# pressure_mat_try1.net
KiCad netlist of a schematic drawn in EAGLE
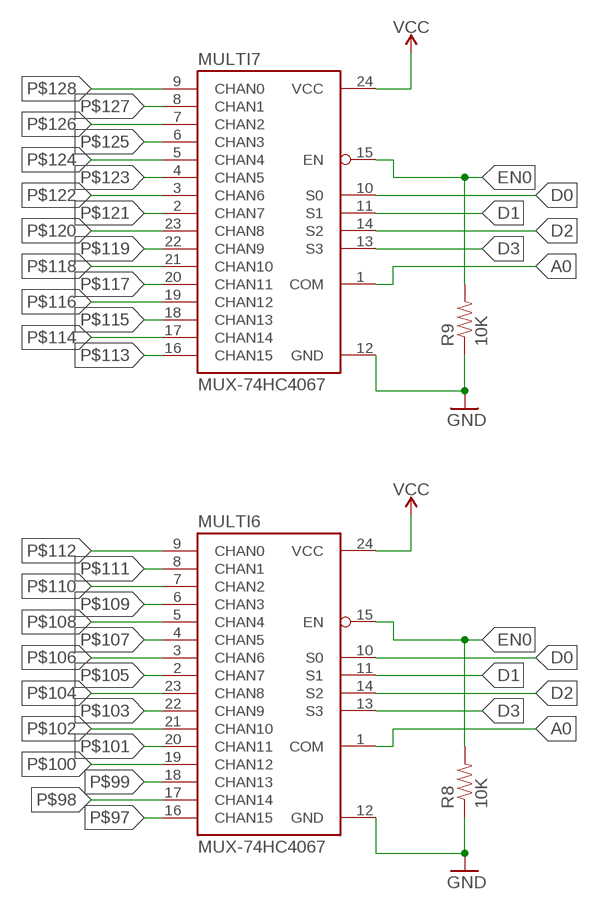
[diagram p0: schematic, sheet 1, part 1 of 3]
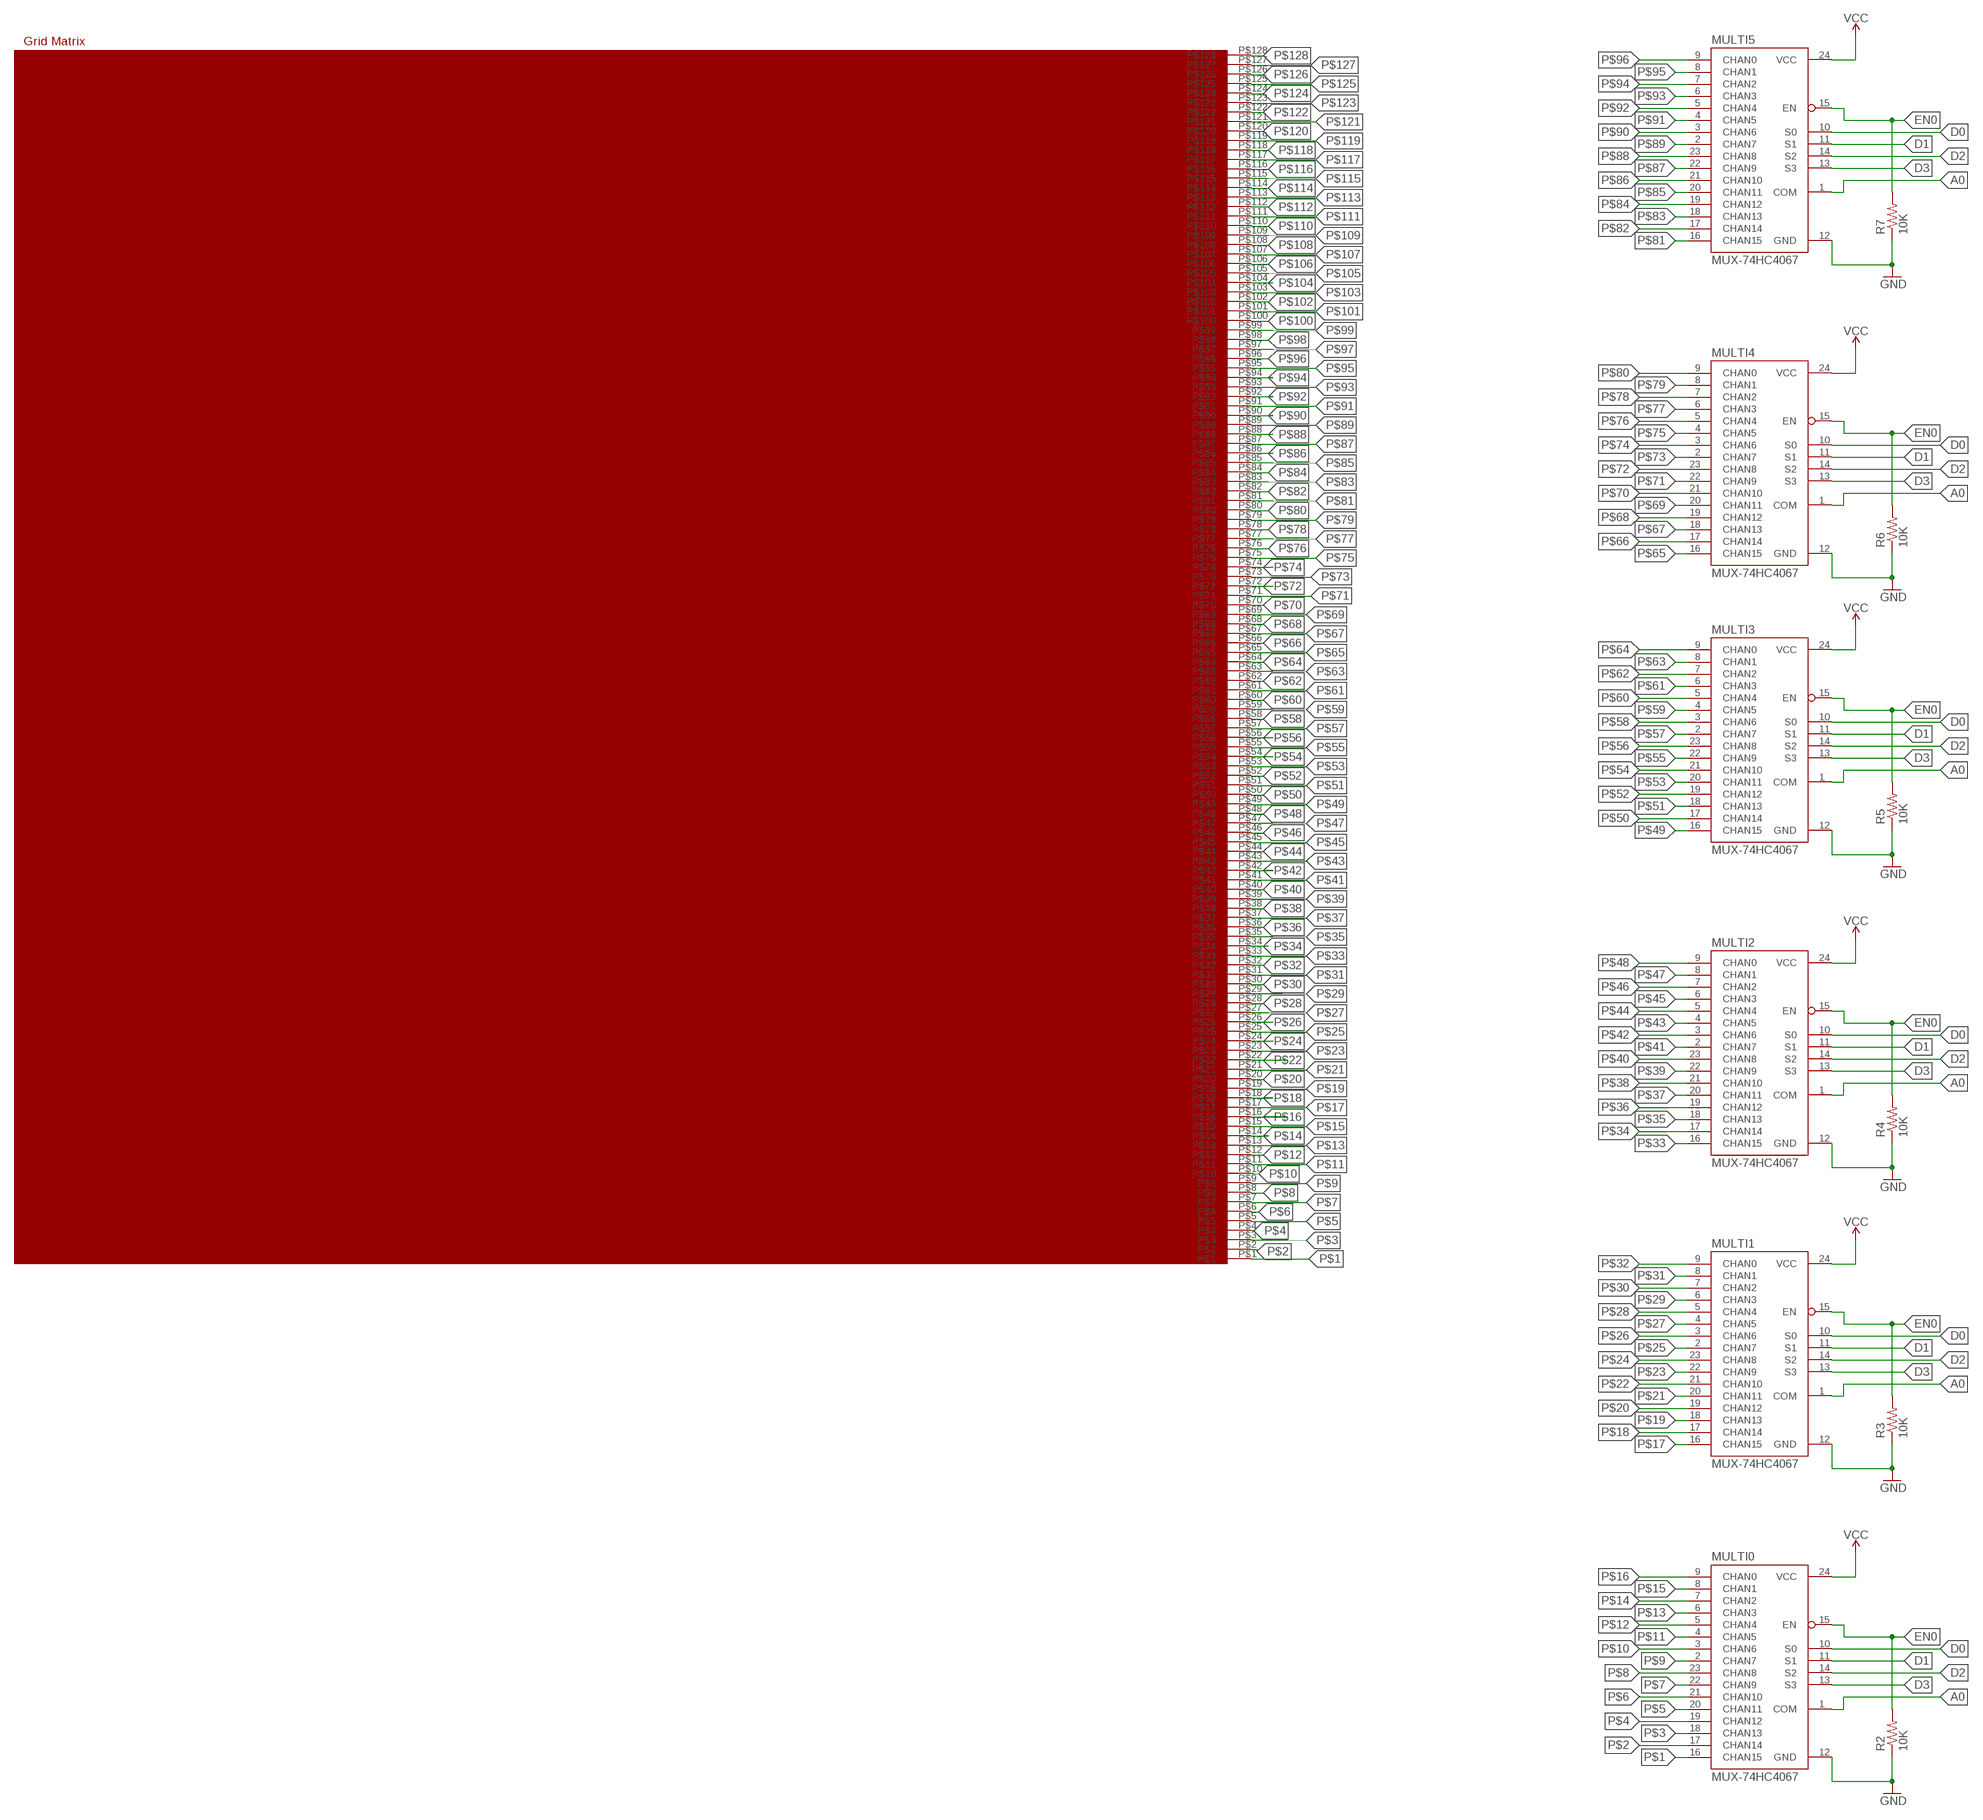
[diagram p1: schematic, sheet 1, part 2 of 3]
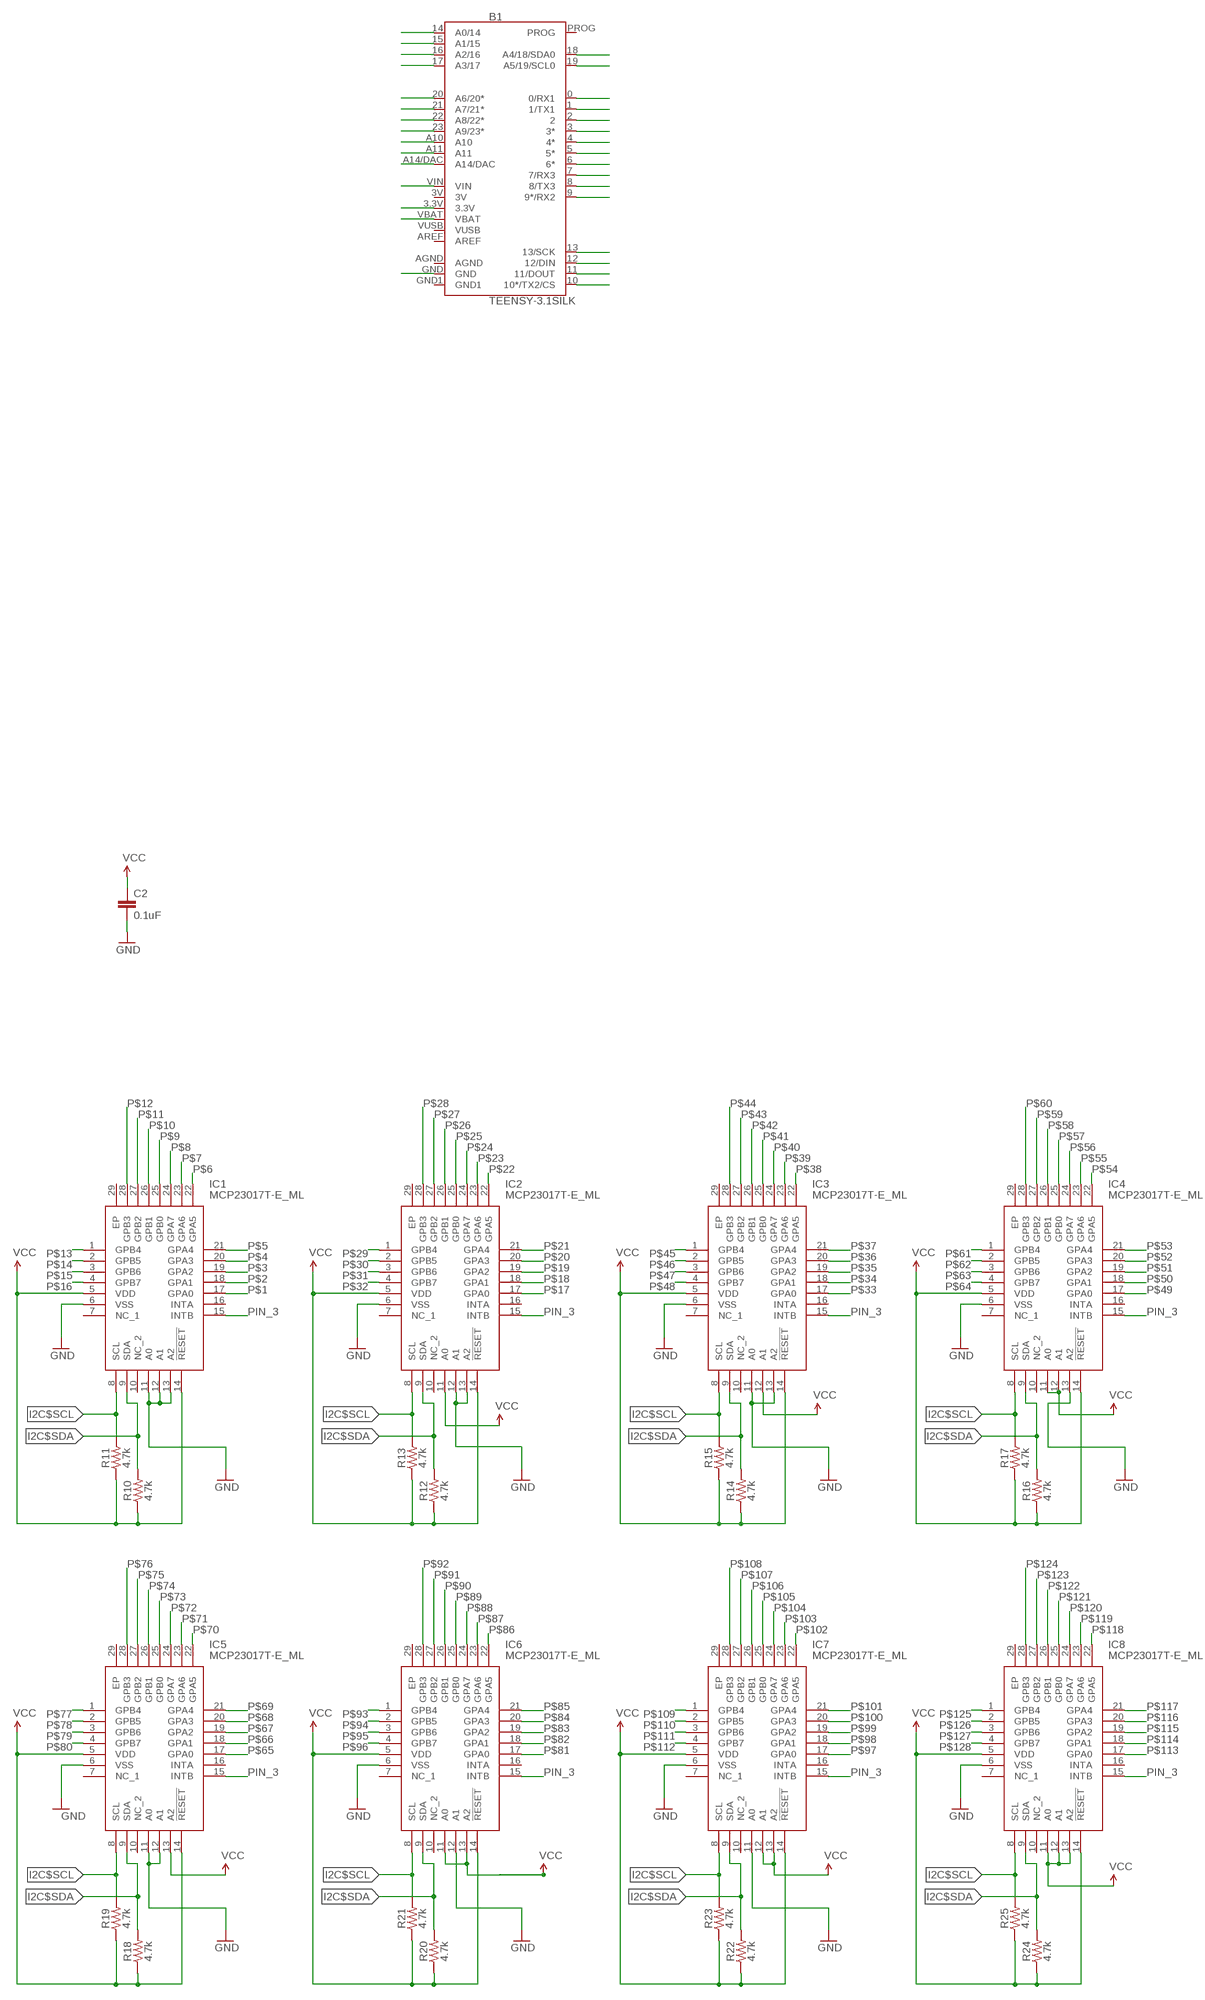
[diagram p2: schematic, sheet 1, part 3 of 3]
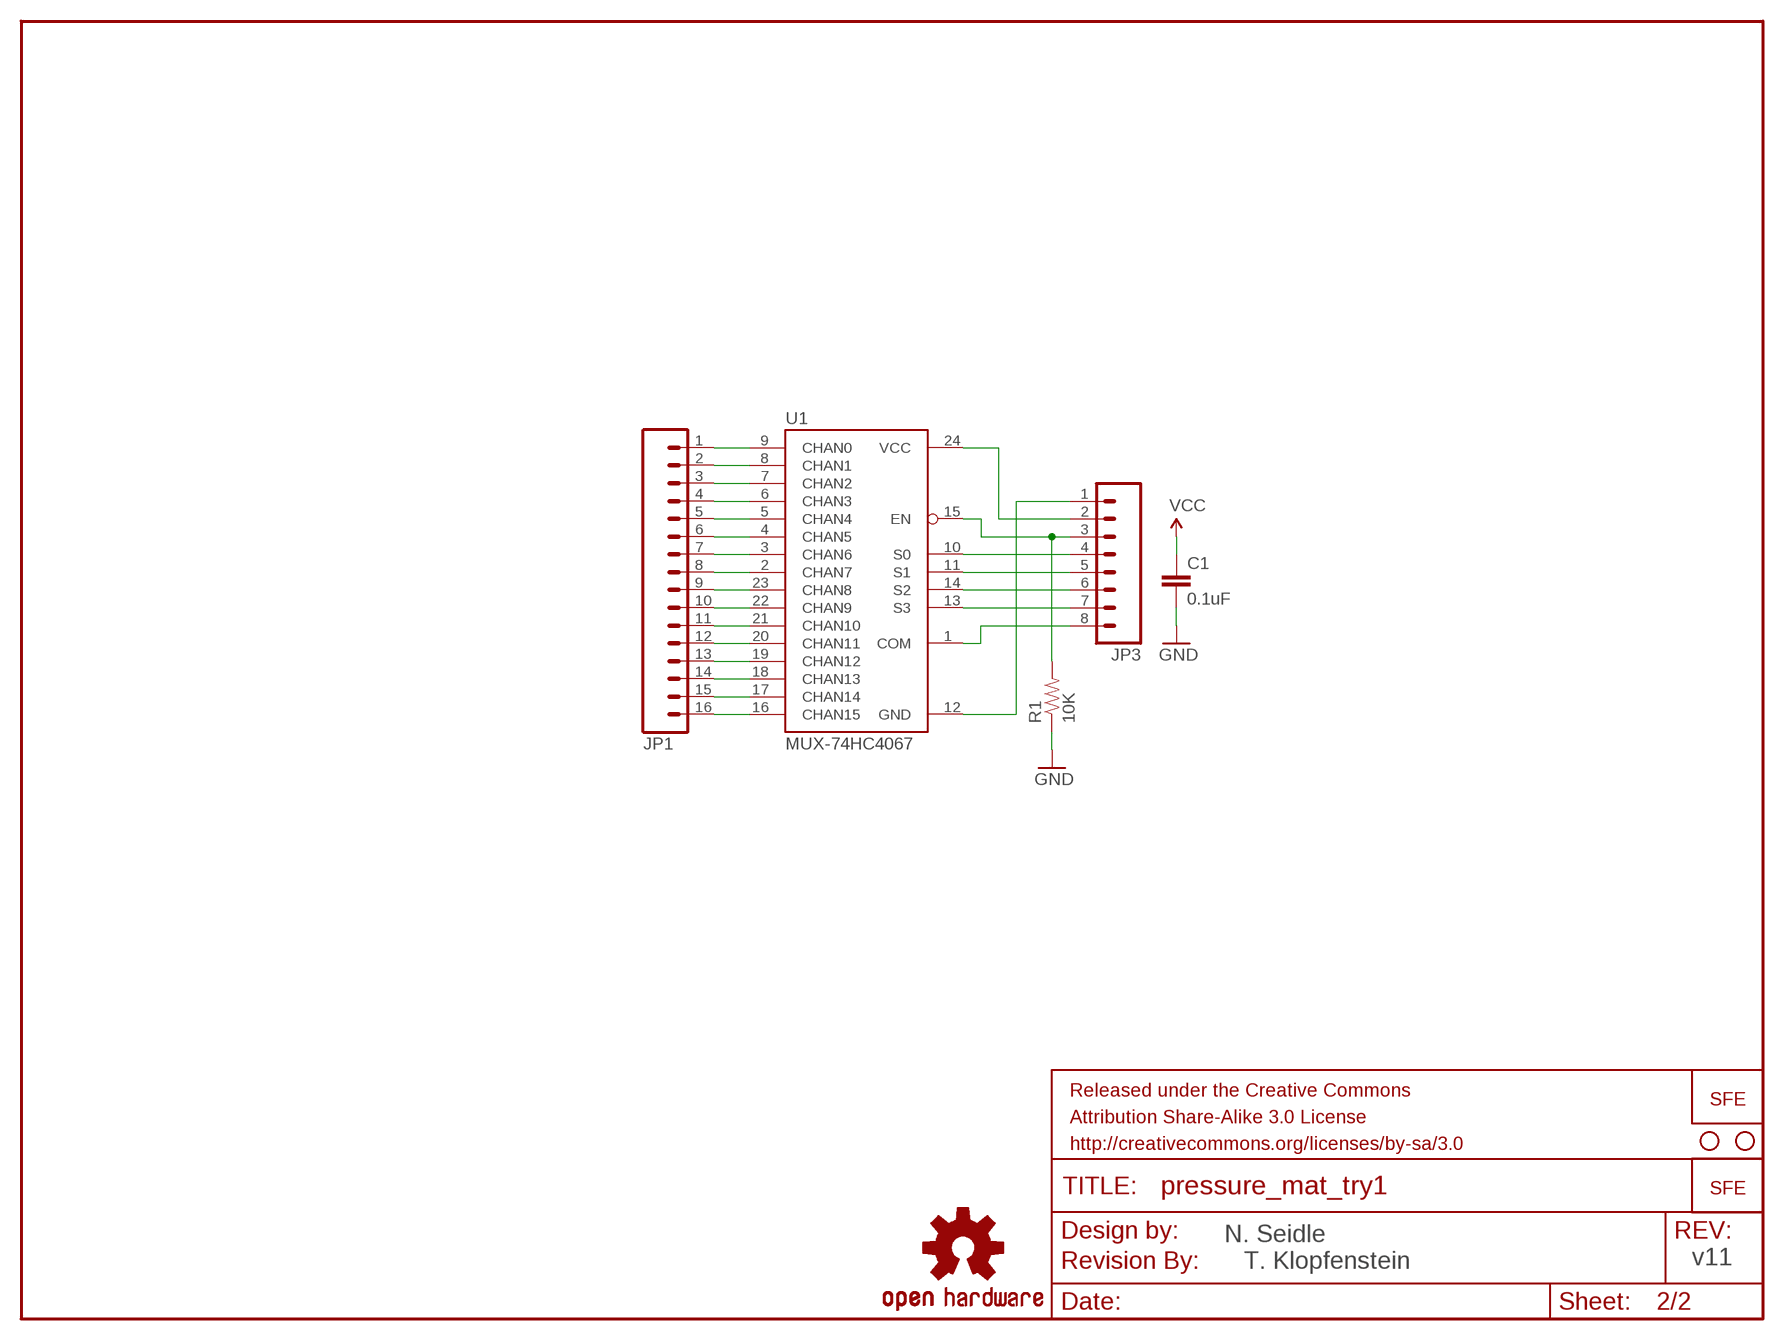
[diagram p3: schematic, sheet 2]

(export (version "E")
  (design (tool "Eeschema 10.0.6"))
  (components
    (comp (ref "B1")
      (value "TEENSY-3.1SILK")
      (footprint "eagle-import:TEENSY-3.1")
      (libsource (lib "eagle-import") (part "TEENSY-3.1SILK"))
    )
    (comp (ref "C2")
      (value "0.1uF")
      (footprint "eagle-import:0603")
      (libsource (lib "eagle-import") (part "CAP0603"))
    )
    (comp (ref "IC1")
      (value "MCP23017T-E_ML")
      (footprint "eagle-import:QFN65P600X600X100-29N")
      (fields
        (field (name "MANUFACTURER_PART_NUMBER") "MCP23017T-E/ML")
        (field (name "MOUSER_PART_NUMBER") "579-MCP23017T-E/ML")
      )
      (libsource (lib "eagle-import") (part "MCP23017T-E_ML"))
    )
    (comp (ref "IC2")
      (value "MCP23017T-E_ML")
      (footprint "eagle-import:QFN65P600X600X100-29N")
      (fields
        (field (name "MANUFACTURER_PART_NUMBER") "MCP23017T-E/ML")
        (field (name "MOUSER_PART_NUMBER") "579-MCP23017T-E/ML")
      )
      (libsource (lib "eagle-import") (part "MCP23017T-E_ML"))
    )
    (comp (ref "IC3")
      (value "MCP23017T-E_ML")
      (footprint "eagle-import:QFN65P600X600X100-29N")
      (fields
        (field (name "MANUFACTURER_PART_NUMBER") "MCP23017T-E/ML")
        (field (name "MOUSER_PART_NUMBER") "579-MCP23017T-E/ML")
      )
      (libsource (lib "eagle-import") (part "MCP23017T-E_ML"))
    )
    (comp (ref "IC4")
      (value "MCP23017T-E_ML")
      (footprint "eagle-import:QFN65P600X600X100-29N")
      (fields
        (field (name "MANUFACTURER_PART_NUMBER") "MCP23017T-E/ML")
        (field (name "MOUSER_PART_NUMBER") "579-MCP23017T-E/ML")
      )
      (libsource (lib "eagle-import") (part "MCP23017T-E_ML"))
    )
    (comp (ref "IC5")
      (value "MCP23017T-E_ML")
      (footprint "eagle-import:QFN65P600X600X100-29N")
      (fields
        (field (name "MANUFACTURER_PART_NUMBER") "MCP23017T-E/ML")
        (field (name "MOUSER_PART_NUMBER") "579-MCP23017T-E/ML")
      )
      (libsource (lib "eagle-import") (part "MCP23017T-E_ML"))
    )
    (comp (ref "IC6")
      (value "MCP23017T-E_ML")
      (footprint "eagle-import:QFN65P600X600X100-29N")
      (fields
        (field (name "MANUFACTURER_PART_NUMBER") "MCP23017T-E/ML")
        (field (name "MOUSER_PART_NUMBER") "579-MCP23017T-E/ML")
      )
      (libsource (lib "eagle-import") (part "MCP23017T-E_ML"))
    )
    (comp (ref "IC7")
      (value "MCP23017T-E_ML")
      (footprint "eagle-import:QFN65P600X600X100-29N")
      (fields
        (field (name "MANUFACTURER_PART_NUMBER") "MCP23017T-E/ML")
        (field (name "MOUSER_PART_NUMBER") "579-MCP23017T-E/ML")
      )
      (libsource (lib "eagle-import") (part "MCP23017T-E_ML"))
    )
    (comp (ref "IC8")
      (value "MCP23017T-E_ML")
      (footprint "eagle-import:QFN65P600X600X100-29N")
      (fields
        (field (name "MANUFACTURER_PART_NUMBER") "MCP23017T-E/ML")
        (field (name "MOUSER_PART_NUMBER") "579-MCP23017T-E/ML")
      )
      (libsource (lib "eagle-import") (part "MCP23017T-E_ML"))
    )
    (comp (ref "MULTI0")
      (value "MUX-74HC4067")
      (footprint "eagle-import:SSOP24")
      (libsource (lib "eagle-import") (part "MUX-74HC4067SMD"))
    )
    (comp (ref "MULTI1")
      (value "MUX-74HC4067")
      (footprint "eagle-import:SSOP24")
      (libsource (lib "eagle-import") (part "MUX-74HC4067SMD"))
    )
    (comp (ref "MULTI2")
      (value "MUX-74HC4067")
      (footprint "eagle-import:SSOP24")
      (libsource (lib "eagle-import") (part "MUX-74HC4067SMD"))
    )
    (comp (ref "MULTI3")
      (value "MUX-74HC4067")
      (footprint "eagle-import:SSOP24")
      (libsource (lib "eagle-import") (part "MUX-74HC4067SMD"))
    )
    (comp (ref "MULTI4")
      (value "MUX-74HC4067")
      (footprint "eagle-import:SSOP24")
      (libsource (lib "eagle-import") (part "MUX-74HC4067SMD"))
    )
    (comp (ref "MULTI5")
      (value "MUX-74HC4067")
      (footprint "eagle-import:SSOP24")
      (libsource (lib "eagle-import") (part "MUX-74HC4067SMD"))
    )
    (comp (ref "MULTI6")
      (value "MUX-74HC4067")
      (footprint "eagle-import:SSOP24")
      (libsource (lib "eagle-import") (part "MUX-74HC4067SMD"))
    )
    (comp (ref "MULTI7")
      (value "MUX-74HC4067")
      (footprint "eagle-import:SSOP24")
      (libsource (lib "eagle-import") (part "MUX-74HC4067SMD"))
    )
    (comp (ref "R2")
      (value "10K")
      (footprint "eagle-import:0603")
      (libsource (lib "eagle-import") (part "RESISTOR0603"))
    )
    (comp (ref "R3")
      (value "10K")
      (footprint "eagle-import:0603")
      (libsource (lib "eagle-import") (part "RESISTOR0603"))
    )
    (comp (ref "R4")
      (value "10K")
      (footprint "eagle-import:0603")
      (libsource (lib "eagle-import") (part "RESISTOR0603"))
    )
    (comp (ref "R5")
      (value "10K")
      (footprint "eagle-import:0603")
      (libsource (lib "eagle-import") (part "RESISTOR0603"))
    )
    (comp (ref "R6")
      (value "10K")
      (footprint "eagle-import:0603")
      (libsource (lib "eagle-import") (part "RESISTOR0603"))
    )
    (comp (ref "R7")
      (value "10K")
      (footprint "eagle-import:0603")
      (libsource (lib "eagle-import") (part "RESISTOR0603"))
    )
    (comp (ref "R8")
      (value "10K")
      (footprint "eagle-import:0603")
      (libsource (lib "eagle-import") (part "RESISTOR0603"))
    )
    (comp (ref "R9")
      (value "10K")
      (footprint "eagle-import:0603")
      (libsource (lib "eagle-import") (part "RESISTOR0603"))
    )
    (comp (ref "R10")
      (value "4.7k")
      (footprint "eagle-import:0603")
      (libsource (lib "eagle-import") (part "4.7KOHM-0603-1/10W-1%"))
    )
    (comp (ref "R11")
      (value "4.7k")
      (footprint "eagle-import:0603")
      (libsource (lib "eagle-import") (part "4.7KOHM-0603-1/10W-1%"))
    )
    (comp (ref "R12")
      (value "4.7k")
      (footprint "eagle-import:0603")
      (libsource (lib "eagle-import") (part "4.7KOHM-0603-1/10W-1%"))
    )
    (comp (ref "R13")
      (value "4.7k")
      (footprint "eagle-import:0603")
      (libsource (lib "eagle-import") (part "4.7KOHM-0603-1/10W-1%"))
    )
    (comp (ref "R14")
      (value "4.7k")
      (footprint "eagle-import:0603")
      (libsource (lib "eagle-import") (part "4.7KOHM-0603-1/10W-1%"))
    )
    (comp (ref "R15")
      (value "4.7k")
      (footprint "eagle-import:0603")
      (libsource (lib "eagle-import") (part "4.7KOHM-0603-1/10W-1%"))
    )
    (comp (ref "R16")
      (value "4.7k")
      (footprint "eagle-import:0603")
      (libsource (lib "eagle-import") (part "4.7KOHM-0603-1/10W-1%"))
    )
    (comp (ref "R17")
      (value "4.7k")
      (footprint "eagle-import:0603")
      (libsource (lib "eagle-import") (part "4.7KOHM-0603-1/10W-1%"))
    )
    (comp (ref "R18")
      (value "4.7k")
      (footprint "eagle-import:0603")
      (libsource (lib "eagle-import") (part "4.7KOHM-0603-1/10W-1%"))
    )
    (comp (ref "R19")
      (value "4.7k")
      (footprint "eagle-import:0603")
      (libsource (lib "eagle-import") (part "4.7KOHM-0603-1/10W-1%"))
    )
    (comp (ref "R20")
      (value "4.7k")
      (footprint "eagle-import:0603")
      (libsource (lib "eagle-import") (part "4.7KOHM-0603-1/10W-1%"))
    )
    (comp (ref "R21")
      (value "4.7k")
      (footprint "eagle-import:0603")
      (libsource (lib "eagle-import") (part "4.7KOHM-0603-1/10W-1%"))
    )
    (comp (ref "R22")
      (value "4.7k")
      (footprint "eagle-import:0603")
      (libsource (lib "eagle-import") (part "4.7KOHM-0603-1/10W-1%"))
    )
    (comp (ref "R23")
      (value "4.7k")
      (footprint "eagle-import:0603")
      (libsource (lib "eagle-import") (part "4.7KOHM-0603-1/10W-1%"))
    )
    (comp (ref "R24")
      (value "4.7k")
      (footprint "eagle-import:0603")
      (libsource (lib "eagle-import") (part "4.7KOHM-0603-1/10W-1%"))
    )
    (comp (ref "R25")
      (value "4.7k")
      (footprint "eagle-import:0603")
      (libsource (lib "eagle-import") (part "4.7KOHM-0603-1/10W-1%"))
    )
    (comp (ref "U$3")
      (value "SENSOR_GRID_V1.0")
      (footprint "eagle-import:SENSOR_GRID_V1.0")
      (libsource (lib "eagle-import") (part "SENSOR_GRID_V1.0"))
    )
    (comp (ref "C1")
      (value "0.1uF")
      (footprint "eagle-import:0603")
      (libsource (lib "eagle-import") (part "CAP0603"))
    )
    (comp (ref "FRAME1")
      (value "FRAME-LETTER")
      (footprint "eagle-import:CREATIVE_COMMONS")
      (libsource (lib "eagle-import") (part "FRAME-LETTER"))
    )
    (comp (ref "JP1")
      (value "M16PTH")
      (footprint "eagle-import:1X16")
      (libsource (lib "eagle-import") (part "M16PTH"))
    )
    (comp (ref "JP3")
      (value "M081X08")
      (footprint "eagle-import:1X08")
      (libsource (lib "eagle-import") (part "M081X08"))
    )
    (comp (ref "LOGO1")
      (value "OSHW-LOGOL")
      (footprint "eagle-import:OSHW-LOGO-L")
      (libsource (lib "eagle-import") (part "OSHW-LOGOL"))
    )
    (comp (ref "LOGO2")
      (value "LOGO-SFESK")
      (footprint "eagle-import:SFE-LOGO-FLAME")
      (libsource (lib "eagle-import") (part "SparkFun-Aesthetics_LOGO-SFESK"))
    )
    (comp (ref "R1")
      (value "10K")
      (footprint "eagle-import:0603")
      (libsource (lib "eagle-import") (part "RESISTOR0603"))
    )
    (comp (ref "STANDOFF1")
      (value "STAND-OFF")
      (footprint "eagle-import:STAND-OFF")
      (libsource (lib "eagle-import") (part "STAND-OFF"))
    )
    (comp (ref "STANDOFF2")
      (value "STAND-OFF")
      (footprint "eagle-import:STAND-OFF")
      (libsource (lib "eagle-import") (part "STAND-OFF"))
    )
    (comp (ref "U$1")
      (value "LOGO-SFENEW")
      (footprint "eagle-import:SFE-NEW-WEBLOGO")
      (libsource (lib "eagle-import") (part "LOGO-SFENEW"))
    )
    (comp (ref "U$2")
      (value "REVISION")
      (footprint "eagle-import:REVISION")
      (libsource (lib "eagle-import") (part "REVISION"))
    )
    (comp (ref "U1")
      (value "MUX-74HC4067")
      (footprint "eagle-import:SSOP24")
      (libsource (lib "eagle-import") (part "MUX-74HC4067SMD"))
    )
  )
  (nets
    (net (code "1") (name "3V") (class "Default")
      (node (ref "B1") (pin "3V") (pinfunction "3V_3V") (pintype "power_in"))
    )
    (net (code "2") (name "A0") (class "Default")
      (node (ref "MULTI0") (pin "1") (pinfunction "COM_1") (pintype "bidirectional"))
      (node (ref "MULTI1") (pin "1") (pinfunction "COM_1") (pintype "bidirectional"))
      (node (ref "MULTI2") (pin "1") (pinfunction "COM_1") (pintype "bidirectional"))
      (node (ref "MULTI3") (pin "1") (pinfunction "COM_1") (pintype "bidirectional"))
      (node (ref "MULTI4") (pin "1") (pinfunction "COM_1") (pintype "bidirectional"))
      (node (ref "MULTI5") (pin "1") (pinfunction "COM_1") (pintype "bidirectional"))
      (node (ref "MULTI6") (pin "1") (pinfunction "COM_1") (pintype "bidirectional"))
      (node (ref "MULTI7") (pin "1") (pinfunction "COM_1") (pintype "bidirectional"))
    )
    (net (code "3") (name "AGND") (class "Default")
      (node (ref "B1") (pin "AGND") (pinfunction "AGND_AGND") (pintype "power_in"))
    )
    (net (code "4") (name "D0") (class "Default")
      (node (ref "MULTI0") (pin "10") (pinfunction "S0_10") (pintype "input"))
      (node (ref "MULTI1") (pin "10") (pinfunction "S0_10") (pintype "input"))
      (node (ref "MULTI2") (pin "10") (pinfunction "S0_10") (pintype "input"))
      (node (ref "MULTI3") (pin "10") (pinfunction "S0_10") (pintype "input"))
      (node (ref "MULTI4") (pin "10") (pinfunction "S0_10") (pintype "input"))
      (node (ref "MULTI5") (pin "10") (pinfunction "S0_10") (pintype "input"))
      (node (ref "MULTI6") (pin "10") (pinfunction "S0_10") (pintype "input"))
      (node (ref "MULTI7") (pin "10") (pinfunction "S0_10") (pintype "input"))
    )
    (net (code "5") (name "D1") (class "Default")
      (node (ref "MULTI0") (pin "11") (pinfunction "S1_11") (pintype "input"))
      (node (ref "MULTI1") (pin "11") (pinfunction "S1_11") (pintype "input"))
      (node (ref "MULTI2") (pin "11") (pinfunction "S1_11") (pintype "input"))
      (node (ref "MULTI3") (pin "11") (pinfunction "S1_11") (pintype "input"))
      (node (ref "MULTI4") (pin "11") (pinfunction "S1_11") (pintype "input"))
      (node (ref "MULTI5") (pin "11") (pinfunction "S1_11") (pintype "input"))
      (node (ref "MULTI6") (pin "11") (pinfunction "S1_11") (pintype "input"))
      (node (ref "MULTI7") (pin "11") (pinfunction "S1_11") (pintype "input"))
    )
    (net (code "6") (name "D2") (class "Default")
      (node (ref "MULTI0") (pin "14") (pinfunction "S2_14") (pintype "input"))
      (node (ref "MULTI1") (pin "14") (pinfunction "S2_14") (pintype "input"))
      (node (ref "MULTI2") (pin "14") (pinfunction "S2_14") (pintype "input"))
      (node (ref "MULTI3") (pin "14") (pinfunction "S2_14") (pintype "input"))
      (node (ref "MULTI4") (pin "14") (pinfunction "S2_14") (pintype "input"))
      (node (ref "MULTI5") (pin "14") (pinfunction "S2_14") (pintype "input"))
      (node (ref "MULTI6") (pin "14") (pinfunction "S2_14") (pintype "input"))
      (node (ref "MULTI7") (pin "14") (pinfunction "S2_14") (pintype "input"))
    )
    (net (code "7") (name "D3") (class "Default")
      (node (ref "MULTI0") (pin "13") (pinfunction "S3_13") (pintype "input"))
      (node (ref "MULTI1") (pin "13") (pinfunction "S3_13") (pintype "input"))
      (node (ref "MULTI2") (pin "13") (pinfunction "S3_13") (pintype "input"))
      (node (ref "MULTI3") (pin "13") (pinfunction "S3_13") (pintype "input"))
      (node (ref "MULTI4") (pin "13") (pinfunction "S3_13") (pintype "input"))
      (node (ref "MULTI5") (pin "13") (pinfunction "S3_13") (pintype "input"))
      (node (ref "MULTI6") (pin "13") (pinfunction "S3_13") (pintype "input"))
      (node (ref "MULTI7") (pin "13") (pinfunction "S3_13") (pintype "input"))
    )
    (net (code "8") (name "EN0") (class "Default")
      (node (ref "MULTI0") (pin "15") (pinfunction "EN_15") (pintype "input"))
      (node (ref "MULTI1") (pin "15") (pinfunction "EN_15") (pintype "input"))
      (node (ref "MULTI2") (pin "15") (pinfunction "EN_15") (pintype "input"))
      (node (ref "MULTI3") (pin "15") (pinfunction "EN_15") (pintype "input"))
      (node (ref "MULTI4") (pin "15") (pinfunction "EN_15") (pintype "input"))
      (node (ref "MULTI5") (pin "15") (pinfunction "EN_15") (pintype "input"))
      (node (ref "MULTI6") (pin "15") (pinfunction "EN_15") (pintype "input"))
      (node (ref "MULTI7") (pin "15") (pinfunction "EN_15") (pintype "input"))
      (node (ref "R2") (pin "2") (pinfunction "2_2") (pintype "passive"))
      (node (ref "R3") (pin "2") (pinfunction "2_2") (pintype "passive"))
      (node (ref "R4") (pin "2") (pinfunction "2_2") (pintype "passive"))
      (node (ref "R5") (pin "2") (pinfunction "2_2") (pintype "passive"))
      (node (ref "R6") (pin "2") (pinfunction "2_2") (pintype "passive"))
      (node (ref "R7") (pin "2") (pinfunction "2_2") (pintype "passive"))
      (node (ref "R8") (pin "2") (pinfunction "2_2") (pintype "passive"))
      (node (ref "R9") (pin "2") (pinfunction "2_2") (pintype "passive"))
    )
    (net (code "9") (name "GND") (class "Default")
      (node (ref "C1") (pin "2") (pinfunction "2_2") (pintype "passive"))
      (node (ref "C2") (pin "2") (pinfunction "2_2") (pintype "passive"))
      (node (ref "IC1") (pin "11") (pinfunction "A0_11") (pintype "bidirectional"))
      (node (ref "IC1") (pin "12") (pinfunction "A1_12") (pintype "bidirectional"))
      (node (ref "IC1") (pin "13") (pinfunction "A2_13") (pintype "bidirectional"))
      (node (ref "IC1") (pin "6") (pinfunction "VSS_6") (pintype "power_in"))
      (node (ref "IC2") (pin "12") (pinfunction "A1_12") (pintype "bidirectional"))
      (node (ref "IC2") (pin "13") (pinfunction "A2_13") (pintype "bidirectional"))
      (node (ref "IC2") (pin "6") (pinfunction "VSS_6") (pintype "power_in"))
      (node (ref "IC3") (pin "11") (pinfunction "A0_11") (pintype "bidirectional"))
      (node (ref "IC3") (pin "13") (pinfunction "A2_13") (pintype "bidirectional"))
      (node (ref "IC3") (pin "6") (pinfunction "VSS_6") (pintype "power_in"))
      (node (ref "IC4") (pin "13") (pinfunction "A2_13") (pintype "bidirectional"))
      (node (ref "IC4") (pin "6") (pinfunction "VSS_6") (pintype "power_in"))
      (node (ref "IC5") (pin "11") (pinfunction "A0_11") (pintype "bidirectional"))
      (node (ref "IC5") (pin "12") (pinfunction "A1_12") (pintype "bidirectional"))
      (node (ref "IC5") (pin "6") (pinfunction "VSS_6") (pintype "power_in"))
      (node (ref "IC6") (pin "12") (pinfunction "A1_12") (pintype "bidirectional"))
      (node (ref "IC6") (pin "6") (pinfunction "VSS_6") (pintype "power_in"))
      (node (ref "IC7") (pin "11") (pinfunction "A0_11") (pintype "bidirectional"))
      (node (ref "IC7") (pin "6") (pinfunction "VSS_6") (pintype "power_in"))
      (node (ref "IC8") (pin "6") (pinfunction "VSS_6") (pintype "power_in"))
      (node (ref "JP3") (pin "1") (pinfunction "1_1") (pintype "passive"))
      (node (ref "MULTI0") (pin "12") (pinfunction "GND_12") (pintype "bidirectional"))
      (node (ref "MULTI1") (pin "12") (pinfunction "GND_12") (pintype "bidirectional"))
      (node (ref "MULTI2") (pin "12") (pinfunction "GND_12") (pintype "bidirectional"))
      (node (ref "MULTI3") (pin "12") (pinfunction "GND_12") (pintype "bidirectional"))
      (node (ref "MULTI4") (pin "12") (pinfunction "GND_12") (pintype "bidirectional"))
      (node (ref "MULTI5") (pin "12") (pinfunction "GND_12") (pintype "bidirectional"))
      (node (ref "MULTI6") (pin "12") (pinfunction "GND_12") (pintype "bidirectional"))
      (node (ref "MULTI7") (pin "12") (pinfunction "GND_12") (pintype "bidirectional"))
      (node (ref "R1") (pin "1") (pinfunction "1_1") (pintype "passive"))
      (node (ref "R2") (pin "1") (pinfunction "1_1") (pintype "passive"))
      (node (ref "R3") (pin "1") (pinfunction "1_1") (pintype "passive"))
      (node (ref "R4") (pin "1") (pinfunction "1_1") (pintype "passive"))
      (node (ref "R5") (pin "1") (pinfunction "1_1") (pintype "passive"))
      (node (ref "R6") (pin "1") (pinfunction "1_1") (pintype "passive"))
      (node (ref "R7") (pin "1") (pinfunction "1_1") (pintype "passive"))
      (node (ref "R8") (pin "1") (pinfunction "1_1") (pintype "passive"))
      (node (ref "R9") (pin "1") (pinfunction "1_1") (pintype "passive"))
      (node (ref "U1") (pin "12") (pinfunction "GND_12") (pintype "bidirectional"))
    )
    (net (code "10") (name "GND1") (class "Default")
      (node (ref "B1") (pin "GND1") (pinfunction "GND1_GND1") (pintype "power_in"))
    )
    (net (code "11") (name "I2C$SCL") (class "Default")
      (node (ref "IC1") (pin "8") (pinfunction "SCL_8") (pintype "bidirectional"))
      (node (ref "IC2") (pin "8") (pinfunction "SCL_8") (pintype "bidirectional"))
      (node (ref "IC3") (pin "8") (pinfunction "SCL_8") (pintype "bidirectional"))
      (node (ref "IC4") (pin "8") (pinfunction "SCL_8") (pintype "bidirectional"))
      (node (ref "IC5") (pin "8") (pinfunction "SCL_8") (pintype "bidirectional"))
      (node (ref "IC6") (pin "8") (pinfunction "SCL_8") (pintype "bidirectional"))
      (node (ref "IC7") (pin "8") (pinfunction "SCL_8") (pintype "bidirectional"))
      (node (ref "IC8") (pin "8") (pinfunction "SCL_8") (pintype "bidirectional"))
      (node (ref "R11") (pin "2") (pinfunction "2_2") (pintype "passive"))
      (node (ref "R13") (pin "2") (pinfunction "2_2") (pintype "passive"))
      (node (ref "R15") (pin "2") (pinfunction "2_2") (pintype "passive"))
      (node (ref "R17") (pin "2") (pinfunction "2_2") (pintype "passive"))
      (node (ref "R19") (pin "2") (pinfunction "2_2") (pintype "passive"))
      (node (ref "R21") (pin "2") (pinfunction "2_2") (pintype "passive"))
      (node (ref "R23") (pin "2") (pinfunction "2_2") (pintype "passive"))
      (node (ref "R25") (pin "2") (pinfunction "2_2") (pintype "passive"))
    )
    (net (code "12") (name "I2C$SDA") (class "Default")
      (node (ref "IC1") (pin "9") (pinfunction "SDA_9") (pintype "bidirectional"))
      (node (ref "IC2") (pin "9") (pinfunction "SDA_9") (pintype "bidirectional"))
      (node (ref "IC3") (pin "9") (pinfunction "SDA_9") (pintype "bidirectional"))
      (node (ref "IC4") (pin "9") (pinfunction "SDA_9") (pintype "bidirectional"))
      (node (ref "IC5") (pin "9") (pinfunction "SDA_9") (pintype "bidirectional"))
      (node (ref "IC6") (pin "9") (pinfunction "SDA_9") (pintype "bidirectional"))
      (node (ref "IC7") (pin "9") (pinfunction "SDA_9") (pintype "bidirectional"))
      (node (ref "IC8") (pin "9") (pinfunction "SDA_9") (pintype "bidirectional"))
      (node (ref "R10") (pin "2") (pinfunction "2_2") (pintype "passive"))
      (node (ref "R12") (pin "2") (pinfunction "2_2") (pintype "passive"))
      (node (ref "R14") (pin "2") (pinfunction "2_2") (pintype "passive"))
      (node (ref "R16") (pin "2") (pinfunction "2_2") (pintype "passive"))
      (node (ref "R18") (pin "2") (pinfunction "2_2") (pintype "passive"))
      (node (ref "R20") (pin "2") (pinfunction "2_2") (pintype "passive"))
      (node (ref "R22") (pin "2") (pinfunction "2_2") (pintype "passive"))
      (node (ref "R24") (pin "2") (pinfunction "2_2") (pintype "passive"))
    )
    (net (code "13") (name "Net-(U1-CHAN0)") (class "Default")
      (node (ref "JP1") (pin "1") (pinfunction "1_1") (pintype "passive"))
      (node (ref "U1") (pin "9") (pinfunction "CHAN0_9") (pintype "bidirectional"))
    )
    (net (code "14") (name "Net-(U1-CHAN1)") (class "Default")
      (node (ref "JP1") (pin "2") (pinfunction "2_2") (pintype "passive"))
      (node (ref "U1") (pin "8") (pinfunction "CHAN1_8") (pintype "bidirectional"))
    )
    (net (code "15") (name "Net-(U1-CHAN2)") (class "Default")
      (node (ref "JP1") (pin "3") (pinfunction "3_3") (pintype "passive"))
      (node (ref "U1") (pin "7") (pinfunction "CHAN2_7") (pintype "bidirectional"))
    )
    (net (code "16") (name "Net-(U1-CHAN3)") (class "Default")
      (node (ref "JP1") (pin "4") (pinfunction "4_4") (pintype "passive"))
      (node (ref "U1") (pin "6") (pinfunction "CHAN3_6") (pintype "bidirectional"))
    )
    (net (code "17") (name "Net-(U1-CHAN4)") (class "Default")
      (node (ref "JP1") (pin "5") (pinfunction "5_5") (pintype "passive"))
      (node (ref "U1") (pin "5") (pinfunction "CHAN4_5") (pintype "bidirectional"))
    )
    (net (code "18") (name "Net-(U1-CHAN5)") (class "Default")
      (node (ref "JP1") (pin "6") (pinfunction "6_6") (pintype "passive"))
      (node (ref "U1") (pin "4") (pinfunction "CHAN5_4") (pintype "bidirectional"))
    )
    (net (code "19") (name "Net-(U1-CHAN6)") (class "Default")
      (node (ref "JP1") (pin "7") (pinfunction "7_7") (pintype "passive"))
      (node (ref "U1") (pin "3") (pinfunction "CHAN6_3") (pintype "bidirectional"))
    )
    (net (code "20") (name "Net-(U1-CHAN7)") (class "Default")
      (node (ref "JP1") (pin "8") (pinfunction "8_8") (pintype "passive"))
      (node (ref "U1") (pin "2") (pinfunction "CHAN7_2") (pintype "bidirectional"))
    )
    (net (code "21") (name "Net-(U1-CHAN8)") (class "Default")
      (node (ref "JP1") (pin "9") (pinfunction "9_9") (pintype "passive"))
      (node (ref "U1") (pin "23") (pinfunction "CHAN8_23") (pintype "bidirectional"))
    )
    (net (code "22") (name "Net-(U1-CHAN9)") (class "Default")
      (node (ref "JP1") (pin "10") (pinfunction "10_10") (pintype "passive"))
      (node (ref "U1") (pin "22") (pinfunction "CHAN9_22") (pintype "bidirectional"))
    )
    (net (code "23") (name "Net-(U1-CHAN10)") (class "Default")
      (node (ref "JP1") (pin "11") (pinfunction "11_11") (pintype "passive"))
      (node (ref "U1") (pin "21") (pinfunction "CHAN10_21") (pintype "bidirectional"))
    )
    (net (code "24") (name "Net-(U1-CHAN11)") (class "Default")
      (node (ref "JP1") (pin "12") (pinfunction "12_12") (pintype "passive"))
      (node (ref "U1") (pin "20") (pinfunction "CHAN11_20") (pintype "bidirectional"))
    )
    (net (code "25") (name "Net-(U1-CHAN12)") (class "Default")
      (node (ref "JP1") (pin "13") (pinfunction "13_13") (pintype "passive"))
      (node (ref "U1") (pin "19") (pinfunction "CHAN12_19") (pintype "bidirectional"))
    )
    (net (code "26") (name "Net-(U1-CHAN13)") (class "Default")
      (node (ref "JP1") (pin "14") (pinfunction "14_14") (pintype "passive"))
      (node (ref "U1") (pin "18") (pinfunction "CHAN13_18") (pintype "bidirectional"))
    )
    (net (code "27") (name "Net-(U1-CHAN14)") (class "Default")
      (node (ref "JP1") (pin "15") (pinfunction "15_15") (pintype "passive"))
      (node (ref "U1") (pin "17") (pinfunction "CHAN14_17") (pintype "bidirectional"))
    )
    (net (code "28") (name "Net-(U1-CHAN15)") (class "Default")
      (node (ref "JP1") (pin "16") (pinfunction "16_16") (pintype "passive"))
      (node (ref "U1") (pin "16") (pinfunction "CHAN15_16") (pintype "bidirectional"))
    )
    (net (code "29") (name "Net-(U1-COM)") (class "Default")
      (node (ref "JP3") (pin "8") (pinfunction "8_8") (pintype "passive"))
      (node (ref "U1") (pin "1") (pinfunction "COM_1") (pintype "bidirectional"))
    )
    (net (code "30") (name "Net-(U1-EN)") (class "Default")
      (node (ref "JP3") (pin "3") (pinfunction "3_3") (pintype "passive"))
      (node (ref "R1") (pin "2") (pinfunction "2_2") (pintype "passive"))
      (node (ref "U1") (pin "15") (pinfunction "EN_15") (pintype "input"))
    )
    (net (code "31") (name "Net-(U1-S0)") (class "Default")
      (node (ref "JP3") (pin "4") (pinfunction "4_4") (pintype "passive"))
      (node (ref "U1") (pin "10") (pinfunction "S0_10") (pintype "input"))
    )
    (net (code "32") (name "Net-(U1-S1)") (class "Default")
      (node (ref "JP3") (pin "5") (pinfunction "5_5") (pintype "passive"))
      (node (ref "U1") (pin "11") (pinfunction "S1_11") (pintype "input"))
    )
    (net (code "33") (name "Net-(U1-S2)") (class "Default")
      (node (ref "JP3") (pin "6") (pinfunction "6_6") (pintype "passive"))
      (node (ref "U1") (pin "14") (pinfunction "S2_14") (pintype "input"))
    )
    (net (code "34") (name "Net-(U1-S3)") (class "Default")
      (node (ref "JP3") (pin "7") (pinfunction "7_7") (pintype "passive"))
      (node (ref "U1") (pin "13") (pinfunction "S3_13") (pintype "input"))
    )
    (net (code "35") (name "P$1") (class "Default")
      (node (ref "IC1") (pin "17") (pinfunction "GPA0_17") (pintype "bidirectional"))
      (node (ref "MULTI0") (pin "16") (pinfunction "CHAN15_16") (pintype "bidirectional"))
      (node (ref "U$3") (pin "P$1") (pinfunction "P$1_P$1") (pintype "bidirectional"))
    )
    (net (code "36") (name "P$2") (class "Default")
      (node (ref "IC1") (pin "18") (pinfunction "GPA1_18") (pintype "bidirectional"))
      (node (ref "MULTI0") (pin "17") (pinfunction "CHAN14_17") (pintype "bidirectional"))
      (node (ref "U$3") (pin "P$2") (pinfunction "P$2_P$2") (pintype "bidirectional"))
    )
    (net (code "37") (name "P$3") (class "Default")
      (node (ref "IC1") (pin "19") (pinfunction "GPA2_19") (pintype "bidirectional"))
      (node (ref "MULTI0") (pin "18") (pinfunction "CHAN13_18") (pintype "bidirectional"))
      (node (ref "U$3") (pin "P$3") (pinfunction "P$3_P$3") (pintype "bidirectional"))
    )
    (net (code "38") (name "P$4") (class "Default")
      (node (ref "IC1") (pin "20") (pinfunction "GPA3_20") (pintype "bidirectional"))
      (node (ref "MULTI0") (pin "19") (pinfunction "CHAN12_19") (pintype "bidirectional"))
      (node (ref "U$3") (pin "P$4") (pinfunction "P$4_P$4") (pintype "bidirectional"))
    )
    (net (code "39") (name "P$5") (class "Default")
      (node (ref "IC1") (pin "21") (pinfunction "GPA4_21") (pintype "bidirectional"))
      (node (ref "MULTI0") (pin "20") (pinfunction "CHAN11_20") (pintype "bidirectional"))
      (node (ref "U$3") (pin "P$5") (pinfunction "P$5_P$5") (pintype "bidirectional"))
    )
    (net (code "40") (name "P$6") (class "Default")
      (node (ref "IC1") (pin "22") (pinfunction "GPA5_22") (pintype "bidirectional"))
      (node (ref "MULTI0") (pin "21") (pinfunction "CHAN10_21") (pintype "bidirectional"))
      (node (ref "U$3") (pin "P$6") (pinfunction "P$6_P$6") (pintype "bidirectional"))
    )
    (net (code "41") (name "P$7") (class "Default")
      (node (ref "IC1") (pin "23") (pinfunction "GPA6_23") (pintype "bidirectional"))
      (node (ref "MULTI0") (pin "22") (pinfunction "CHAN9_22") (pintype "bidirectional"))
      (node (ref "U$3") (pin "P$7") (pinfunction "P$7_P$7") (pintype "bidirectional"))
    )
    (net (code "42") (name "P$8") (class "Default")
      (node (ref "IC1") (pin "24") (pinfunction "GPA7_24") (pintype "bidirectional"))
      (node (ref "MULTI0") (pin "23") (pinfunction "CHAN8_23") (pintype "bidirectional"))
      (node (ref "U$3") (pin "P$8") (pinfunction "P$8_P$8") (pintype "bidirectional"))
    )
    (net (code "43") (name "P$9") (class "Default")
      (node (ref "IC1") (pin "25") (pinfunction "GPB0_25") (pintype "bidirectional"))
      (node (ref "MULTI0") (pin "2") (pinfunction "CHAN7_2") (pintype "bidirectional"))
      (node (ref "U$3") (pin "P$9") (pinfunction "P$9_P$9") (pintype "bidirectional"))
    )
    (net (code "44") (name "P$10") (class "Default")
      (node (ref "IC1") (pin "26") (pinfunction "GPB1_26") (pintype "bidirectional"))
      (node (ref "MULTI0") (pin "3") (pinfunction "CHAN6_3") (pintype "bidirectional"))
      (node (ref "U$3") (pin "P$10") (pinfunction "P$10_P$10") (pintype "bidirectional"))
    )
    (net (code "45") (name "P$11") (class "Default")
      (node (ref "IC1") (pin "27") (pinfunction "GPB2_27") (pintype "bidirectional"))
      (node (ref "MULTI0") (pin "4") (pinfunction "CHAN5_4") (pintype "bidirectional"))
      (node (ref "U$3") (pin "P$11") (pinfunction "P$11_P$11") (pintype "bidirectional"))
    )
    (net (code "46") (name "P$12") (class "Default")
      (node (ref "IC1") (pin "28") (pinfunction "GPB3_28") (pintype "bidirectional"))
      (node (ref "MULTI0") (pin "5") (pinfunction "CHAN4_5") (pintype "bidirectional"))
      (node (ref "U$3") (pin "P$12") (pinfunction "P$12_P$12") (pintype "bidirectional"))
    )
    (net (code "47") (name "P$13") (class "Default")
      (node (ref "IC1") (pin "1") (pinfunction "GPB4_1") (pintype "bidirectional"))
      (node (ref "MULTI0") (pin "6") (pinfunction "CHAN3_6") (pintype "bidirectional"))
      (node (ref "U$3") (pin "P$13") (pinfunction "P$13_P$13") (pintype "bidirectional"))
    )
    (net (code "48") (name "P$14") (class "Default")
      (node (ref "IC1") (pin "2") (pinfunction "GPB5_2") (pintype "bidirectional"))
      (node (ref "MULTI0") (pin "7") (pinfunction "CHAN2_7") (pintype "bidirectional"))
      (node (ref "U$3") (pin "P$14") (pinfunction "P$14_P$14") (pintype "bidirectional"))
    )
    (net (code "49") (name "P$15") (class "Default")
      (node (ref "IC1") (pin "3") (pinfunction "GPB6_3") (pintype "bidirectional"))
      (node (ref "MULTI0") (pin "8") (pinfunction "CHAN1_8") (pintype "bidirectional"))
      (node (ref "U$3") (pin "P$15") (pinfunction "P$15_P$15") (pintype "bidirectional"))
    )
    (net (code "50") (name "P$16") (class "Default")
      (node (ref "IC1") (pin "4") (pinfunction "GPB7_4") (pintype "bidirectional"))
      (node (ref "MULTI0") (pin "9") (pinfunction "CHAN0_9") (pintype "bidirectional"))
      (node (ref "U$3") (pin "P$16") (pinfunction "P$16_P$16") (pintype "bidirectional"))
    )
    (net (code "51") (name "P$17") (class "Default")
      (node (ref "IC2") (pin "17") (pinfunction "GPA0_17") (pintype "bidirectional"))
      (node (ref "MULTI1") (pin "16") (pinfunction "CHAN15_16") (pintype "bidirectional"))
      (node (ref "U$3") (pin "P$17") (pinfunction "P$17_P$17") (pintype "bidirectional"))
    )
    (net (code "52") (name "P$18") (class "Default")
      (node (ref "IC2") (pin "18") (pinfunction "GPA1_18") (pintype "bidirectional"))
      (node (ref "MULTI1") (pin "17") (pinfunction "CHAN14_17") (pintype "bidirectional"))
      (node (ref "U$3") (pin "P$18") (pinfunction "P$18_P$18") (pintype "bidirectional"))
    )
    (net (code "53") (name "P$19") (class "Default")
      (node (ref "IC2") (pin "19") (pinfunction "GPA2_19") (pintype "bidirectional"))
      (node (ref "MULTI1") (pin "18") (pinfunction "CHAN13_18") (pintype "bidirectional"))
      (node (ref "U$3") (pin "P$19") (pinfunction "P$19_P$19") (pintype "bidirectional"))
    )
    (net (code "54") (name "P$20") (class "Default")
      (node (ref "IC2") (pin "20") (pinfunction "GPA3_20") (pintype "bidirectional"))
      (node (ref "MULTI1") (pin "19") (pinfunction "CHAN12_19") (pintype "bidirectional"))
      (node (ref "U$3") (pin "P$20") (pinfunction "P$20_P$20") (pintype "bidirectional"))
    )
    (net (code "55") (name "P$21") (class "Default")
      (node (ref "IC2") (pin "21") (pinfunction "GPA4_21") (pintype "bidirectional"))
      (node (ref "MULTI1") (pin "20") (pinfunction "CHAN11_20") (pintype "bidirectional"))
      (node (ref "U$3") (pin "P$21") (pinfunction "P$21_P$21") (pintype "bidirectional"))
    )
    (net (code "56") (name "P$22") (class "Default")
      (node (ref "IC2") (pin "22") (pinfunction "GPA5_22") (pintype "bidirectional"))
      (node (ref "MULTI1") (pin "21") (pinfunction "CHAN10_21") (pintype "bidirectional"))
      (node (ref "U$3") (pin "P$22") (pinfunction "P$22_P$22") (pintype "bidirectional"))
    )
    (net (code "57") (name "P$23") (class "Default")
      (node (ref "IC2") (pin "23") (pinfunction "GPA6_23") (pintype "bidirectional"))
      (node (ref "MULTI1") (pin "22") (pinfunction "CHAN9_22") (pintype "bidirectional"))
      (node (ref "U$3") (pin "P$23") (pinfunction "P$23_P$23") (pintype "bidirectional"))
    )
    (net (code "58") (name "P$24") (class "Default")
      (node (ref "IC2") (pin "24") (pinfunction "GPA7_24") (pintype "bidirectional"))
      (node (ref "MULTI1") (pin "23") (pinfunction "CHAN8_23") (pintype "bidirectional"))
      (node (ref "U$3") (pin "P$24") (pinfunction "P$24_P$24") (pintype "bidirectional"))
    )
    (net (code "59") (name "P$25") (class "Default")
      (node (ref "IC2") (pin "25") (pinfunction "GPB0_25") (pintype "bidirectional"))
      (node (ref "MULTI1") (pin "2") (pinfunction "CHAN7_2") (pintype "bidirectional"))
      (node (ref "U$3") (pin "P$25") (pinfunction "P$25_P$25") (pintype "bidirectional"))
    )
    (net (code "60") (name "P$26") (class "Default")
      (node (ref "IC2") (pin "26") (pinfunction "GPB1_26") (pintype "bidirectional"))
      (node (ref "MULTI1") (pin "3") (pinfunction "CHAN6_3") (pintype "bidirectional"))
      (node (ref "U$3") (pin "P$26") (pinfunction "P$26_P$26") (pintype "bidirectional"))
    )
    (net (code "61") (name "P$27") (class "Default")
      (node (ref "IC2") (pin "27") (pinfunction "GPB2_27") (pintype "bidirectional"))
      (node (ref "MULTI1") (pin "4") (pinfunction "CHAN5_4") (pintype "bidirectional"))
      (node (ref "U$3") (pin "P$27") (pinfunction "P$27_P$27") (pintype "bidirectional"))
    )
    (net (code "62") (name "P$28") (class "Default")
      (node (ref "IC2") (pin "28") (pinfunction "GPB3_28") (pintype "bidirectional"))
      (node (ref "MULTI1") (pin "5") (pinfunction "CHAN4_5") (pintype "bidirectional"))
      (node (ref "U$3") (pin "P$28") (pinfunction "P$28_P$28") (pintype "bidirectional"))
    )
    (net (code "63") (name "P$29") (class "Default")
      (node (ref "IC2") (pin "1") (pinfunction "GPB4_1") (pintype "bidirectional"))
      (node (ref "MULTI1") (pin "6") (pinfunction "CHAN3_6") (pintype "bidirectional"))
      (node (ref "U$3") (pin "P$29") (pinfunction "P$29_P$29") (pintype "bidirectional"))
    )
    (net (code "64") (name "P$30") (class "Default")
      (node (ref "IC2") (pin "2") (pinfunction "GPB5_2") (pintype "bidirectional"))
      (node (ref "MULTI1") (pin "7") (pinfunction "CHAN2_7") (pintype "bidirectional"))
      (node (ref "U$3") (pin "P$30") (pinfunction "P$30_P$30") (pintype "bidirectional"))
    )
    (net (code "65") (name "P$31") (class "Default")
      (node (ref "IC2") (pin "3") (pinfunction "GPB6_3") (pintype "bidirectional"))
      (node (ref "MULTI1") (pin "8") (pinfunction "CHAN1_8") (pintype "bidirectional"))
      (node (ref "U$3") (pin "P$31") (pinfunction "P$31_P$31") (pintype "bidirectional"))
    )
    (net (code "66") (name "P$32") (class "Default")
      (node (ref "IC2") (pin "4") (pinfunction "GPB7_4") (pintype "bidirectional"))
      (node (ref "MULTI1") (pin "9") (pinfunction "CHAN0_9") (pintype "bidirectional"))
      (node (ref "U$3") (pin "P$32") (pinfunction "P$32_P$32") (pintype "bidirectional"))
    )
    (net (code "67") (name "P$33") (class "Default")
      (node (ref "IC3") (pin "17") (pinfunction "GPA0_17") (pintype "bidirectional"))
      (node (ref "MULTI2") (pin "16") (pinfunction "CHAN15_16") (pintype "bidirectional"))
      (node (ref "U$3") (pin "P$33") (pinfunction "P$33_P$33") (pintype "bidirectional"))
    )
    (net (code "68") (name "P$34") (class "Default")
      (node (ref "IC3") (pin "18") (pinfunction "GPA1_18") (pintype "bidirectional"))
      (node (ref "MULTI2") (pin "17") (pinfunction "CHAN14_17") (pintype "bidirectional"))
      (node (ref "U$3") (pin "P$34") (pinfunction "P$34_P$34") (pintype "bidirectional"))
    )
    (net (code "69") (name "P$35") (class "Default")
      (node (ref "IC3") (pin "19") (pinfunction "GPA2_19") (pintype "bidirectional"))
      (node (ref "MULTI2") (pin "18") (pinfunction "CHAN13_18") (pintype "bidirectional"))
      (node (ref "U$3") (pin "P$35") (pinfunction "P$35_P$35") (pintype "bidirectional"))
    )
    (net (code "70") (name "P$36") (class "Default")
      (node (ref "IC3") (pin "20") (pinfunction "GPA3_20") (pintype "bidirectional"))
      (node (ref "MULTI2") (pin "19") (pinfunction "CHAN12_19") (pintype "bidirectional"))
      (node (ref "U$3") (pin "P$36") (pinfunction "P$36_P$36") (pintype "bidirectional"))
    )
    (net (code "71") (name "P$37") (class "Default")
      (node (ref "IC3") (pin "21") (pinfunction "GPA4_21") (pintype "bidirectional"))
      (node (ref "MULTI2") (pin "20") (pinfunction "CHAN11_20") (pintype "bidirectional"))
      (node (ref "U$3") (pin "P$37") (pinfunction "P$37_P$37") (pintype "bidirectional"))
    )
    (net (code "72") (name "P$38") (class "Default")
      (node (ref "IC3") (pin "22") (pinfunction "GPA5_22") (pintype "bidirectional"))
      (node (ref "MULTI2") (pin "21") (pinfunction "CHAN10_21") (pintype "bidirectional"))
      (node (ref "U$3") (pin "P$38") (pinfunction "P$38_P$38") (pintype "bidirectional"))
    )
    (net (code "73") (name "P$39") (class "Default")
      (node (ref "IC3") (pin "23") (pinfunction "GPA6_23") (pintype "bidirectional"))
      (node (ref "MULTI2") (pin "22") (pinfunction "CHAN9_22") (pintype "bidirectional"))
      (node (ref "U$3") (pin "P$39") (pinfunction "P$39_P$39") (pintype "bidirectional"))
    )
    (net (code "74") (name "P$40") (class "Default")
      (node (ref "IC3") (pin "24") (pinfunction "GPA7_24") (pintype "bidirectional"))
      (node (ref "MULTI2") (pin "23") (pinfunction "CHAN8_23") (pintype "bidirectional"))
      (node (ref "U$3") (pin "P$40") (pinfunction "P$40_P$40") (pintype "bidirectional"))
    )
    (net (code "75") (name "P$41") (class "Default")
      (node (ref "IC3") (pin "25") (pinfunction "GPB0_25") (pintype "bidirectional"))
      (node (ref "MULTI2") (pin "2") (pinfunction "CHAN7_2") (pintype "bidirectional"))
      (node (ref "U$3") (pin "P$41") (pinfunction "P$41_P$41") (pintype "bidirectional"))
    )
    (net (code "76") (name "P$42") (class "Default")
      (node (ref "IC3") (pin "26") (pinfunction "GPB1_26") (pintype "bidirectional"))
      (node (ref "MULTI2") (pin "3") (pinfunction "CHAN6_3") (pintype "bidirectional"))
      (node (ref "U$3") (pin "P$42") (pinfunction "P$42_P$42") (pintype "bidirectional"))
    )
    (net (code "77") (name "P$43") (class "Default")
      (node (ref "IC3") (pin "27") (pinfunction "GPB2_27") (pintype "bidirectional"))
      (node (ref "MULTI2") (pin "4") (pinfunction "CHAN5_4") (pintype "bidirectional"))
      (node (ref "U$3") (pin "P$43") (pinfunction "P$43_P$43") (pintype "bidirectional"))
    )
    (net (code "78") (name "P$44") (class "Default")
      (node (ref "IC3") (pin "28") (pinfunction "GPB3_28") (pintype "bidirectional"))
      (node (ref "MULTI2") (pin "5") (pinfunction "CHAN4_5") (pintype "bidirectional"))
      (node (ref "U$3") (pin "P$44") (pinfunction "P$44_P$44") (pintype "bidirectional"))
    )
    (net (code "79") (name "P$45") (class "Default")
      (node (ref "IC3") (pin "1") (pinfunction "GPB4_1") (pintype "bidirectional"))
      (node (ref "MULTI2") (pin "6") (pinfunction "CHAN3_6") (pintype "bidirectional"))
      (node (ref "U$3") (pin "P$45") (pinfunction "P$45_P$45") (pintype "bidirectional"))
    )
    (net (code "80") (name "P$46") (class "Default")
      (node (ref "IC3") (pin "2") (pinfunction "GPB5_2") (pintype "bidirectional"))
      (node (ref "MULTI2") (pin "7") (pinfunction "CHAN2_7") (pintype "bidirectional"))
      (node (ref "U$3") (pin "P$46") (pinfunction "P$46_P$46") (pintype "bidirectional"))
    )
    (net (code "81") (name "P$47") (class "Default")
      (node (ref "IC3") (pin "3") (pinfunction "GPB6_3") (pintype "bidirectional"))
      (node (ref "MULTI2") (pin "8") (pinfunction "CHAN1_8") (pintype "bidirectional"))
      (node (ref "U$3") (pin "P$47") (pinfunction "P$47_P$47") (pintype "bidirectional"))
    )
    (net (code "82") (name "P$48") (class "Default")
      (node (ref "IC3") (pin "4") (pinfunction "GPB7_4") (pintype "bidirectional"))
      (node (ref "MULTI2") (pin "9") (pinfunction "CHAN0_9") (pintype "bidirectional"))
      (node (ref "U$3") (pin "P$48") (pinfunction "P$48_P$48") (pintype "bidirectional"))
    )
    (net (code "83") (name "P$49") (class "Default")
      (node (ref "IC4") (pin "17") (pinfunction "GPA0_17") (pintype "bidirectional"))
      (node (ref "MULTI3") (pin "16") (pinfunction "CHAN15_16") (pintype "bidirectional"))
      (node (ref "U$3") (pin "P$49") (pinfunction "P$49_P$49") (pintype "bidirectional"))
    )
    (net (code "84") (name "P$50") (class "Default")
      (node (ref "IC4") (pin "18") (pinfunction "GPA1_18") (pintype "bidirectional"))
      (node (ref "MULTI3") (pin "17") (pinfunction "CHAN14_17") (pintype "bidirectional"))
      (node (ref "U$3") (pin "P$50") (pinfunction "P$50_P$50") (pintype "bidirectional"))
    )
    (net (code "85") (name "P$51") (class "Default")
      (node (ref "IC4") (pin "19") (pinfunction "GPA2_19") (pintype "bidirectional"))
      (node (ref "MULTI3") (pin "18") (pinfunction "CHAN13_18") (pintype "bidirectional"))
      (node (ref "U$3") (pin "P$51") (pinfunction "P$51_P$51") (pintype "bidirectional"))
    )
    (net (code "86") (name "P$52") (class "Default")
      (node (ref "IC4") (pin "20") (pinfunction "GPA3_20") (pintype "bidirectional"))
      (node (ref "MULTI3") (pin "19") (pinfunction "CHAN12_19") (pintype "bidirectional"))
      (node (ref "U$3") (pin "P$52") (pinfunction "P$52_P$52") (pintype "bidirectional"))
    )
    (net (code "87") (name "P$53") (class "Default")
      (node (ref "IC4") (pin "21") (pinfunction "GPA4_21") (pintype "bidirectional"))
      (node (ref "MULTI3") (pin "20") (pinfunction "CHAN11_20") (pintype "bidirectional"))
      (node (ref "U$3") (pin "P$53") (pinfunction "P$53_P$53") (pintype "bidirectional"))
    )
    (net (code "88") (name "P$54") (class "Default")
      (node (ref "IC4") (pin "22") (pinfunction "GPA5_22") (pintype "bidirectional"))
      (node (ref "MULTI3") (pin "21") (pinfunction "CHAN10_21") (pintype "bidirectional"))
      (node (ref "U$3") (pin "P$54") (pinfunction "P$54_P$54") (pintype "bidirectional"))
    )
    (net (code "89") (name "P$55") (class "Default")
      (node (ref "IC4") (pin "23") (pinfunction "GPA6_23") (pintype "bidirectional"))
      (node (ref "MULTI3") (pin "22") (pinfunction "CHAN9_22") (pintype "bidirectional"))
      (node (ref "U$3") (pin "P$55") (pinfunction "P$55_P$55") (pintype "bidirectional"))
    )
    (net (code "90") (name "P$56") (class "Default")
      (node (ref "IC4") (pin "24") (pinfunction "GPA7_24") (pintype "bidirectional"))
      (node (ref "MULTI3") (pin "23") (pinfunction "CHAN8_23") (pintype "bidirectional"))
      (node (ref "U$3") (pin "P$56") (pinfunction "P$56_P$56") (pintype "bidirectional"))
    )
    (net (code "91") (name "P$57") (class "Default")
      (node (ref "IC4") (pin "25") (pinfunction "GPB0_25") (pintype "bidirectional"))
      (node (ref "MULTI3") (pin "2") (pinfunction "CHAN7_2") (pintype "bidirectional"))
      (node (ref "U$3") (pin "P$57") (pinfunction "P$57_P$57") (pintype "bidirectional"))
    )
    (net (code "92") (name "P$58") (class "Default")
      (node (ref "IC4") (pin "26") (pinfunction "GPB1_26") (pintype "bidirectional"))
      (node (ref "MULTI3") (pin "3") (pinfunction "CHAN6_3") (pintype "bidirectional"))
      (node (ref "U$3") (pin "P$58") (pinfunction "P$58_P$58") (pintype "bidirectional"))
    )
    (net (code "93") (name "P$59") (class "Default")
      (node (ref "IC4") (pin "27") (pinfunction "GPB2_27") (pintype "bidirectional"))
      (node (ref "MULTI3") (pin "4") (pinfunction "CHAN5_4") (pintype "bidirectional"))
      (node (ref "U$3") (pin "P$59") (pinfunction "P$59_P$59") (pintype "bidirectional"))
    )
    (net (code "94") (name "P$60") (class "Default")
      (node (ref "IC4") (pin "28") (pinfunction "GPB3_28") (pintype "bidirectional"))
      (node (ref "MULTI3") (pin "5") (pinfunction "CHAN4_5") (pintype "bidirectional"))
      (node (ref "U$3") (pin "P$60") (pinfunction "P$60_P$60") (pintype "bidirectional"))
    )
    (net (code "95") (name "P$61") (class "Default")
      (node (ref "IC4") (pin "1") (pinfunction "GPB4_1") (pintype "bidirectional"))
      (node (ref "MULTI3") (pin "6") (pinfunction "CHAN3_6") (pintype "bidirectional"))
      (node (ref "U$3") (pin "P$61") (pinfunction "P$61_P$61") (pintype "bidirectional"))
    )
    (net (code "96") (name "P$62") (class "Default")
      (node (ref "IC4") (pin "2") (pinfunction "GPB5_2") (pintype "bidirectional"))
      (node (ref "MULTI3") (pin "7") (pinfunction "CHAN2_7") (pintype "bidirectional"))
      (node (ref "U$3") (pin "P$62") (pinfunction "P$62_P$62") (pintype "bidirectional"))
    )
    (net (code "97") (name "P$63") (class "Default")
      (node (ref "IC4") (pin "3") (pinfunction "GPB6_3") (pintype "bidirectional"))
      (node (ref "MULTI3") (pin "8") (pinfunction "CHAN1_8") (pintype "bidirectional"))
      (node (ref "U$3") (pin "P$63") (pinfunction "P$63_P$63") (pintype "bidirectional"))
    )
    (net (code "98") (name "P$64") (class "Default")
      (node (ref "IC4") (pin "4") (pinfunction "GPB7_4") (pintype "bidirectional"))
      (node (ref "MULTI3") (pin "9") (pinfunction "CHAN0_9") (pintype "bidirectional"))
      (node (ref "U$3") (pin "P$64") (pinfunction "P$64_P$64") (pintype "bidirectional"))
    )
    (net (code "99") (name "P$65") (class "Default")
      (node (ref "IC5") (pin "17") (pinfunction "GPA0_17") (pintype "bidirectional"))
      (node (ref "MULTI4") (pin "16") (pinfunction "CHAN15_16") (pintype "bidirectional"))
      (node (ref "U$3") (pin "P$65") (pinfunction "P$65_P$65") (pintype "bidirectional"))
    )
    (net (code "100") (name "P$66") (class "Default")
      (node (ref "IC5") (pin "18") (pinfunction "GPA1_18") (pintype "bidirectional"))
      (node (ref "MULTI4") (pin "17") (pinfunction "CHAN14_17") (pintype "bidirectional"))
      (node (ref "U$3") (pin "P$66") (pinfunction "P$66_P$66") (pintype "bidirectional"))
    )
    (net (code "101") (name "P$67") (class "Default")
      (node (ref "IC5") (pin "19") (pinfunction "GPA2_19") (pintype "bidirectional"))
      (node (ref "MULTI4") (pin "18") (pinfunction "CHAN13_18") (pintype "bidirectional"))
      (node (ref "U$3") (pin "P$67") (pinfunction "P$67_P$67") (pintype "bidirectional"))
    )
    (net (code "102") (name "P$68") (class "Default")
      (node (ref "IC5") (pin "20") (pinfunction "GPA3_20") (pintype "bidirectional"))
      (node (ref "MULTI4") (pin "19") (pinfunction "CHAN12_19") (pintype "bidirectional"))
      (node (ref "U$3") (pin "P$68") (pinfunction "P$68_P$68") (pintype "bidirectional"))
    )
    (net (code "103") (name "P$69") (class "Default")
      (node (ref "IC5") (pin "21") (pinfunction "GPA4_21") (pintype "bidirectional"))
      (node (ref "MULTI4") (pin "20") (pinfunction "CHAN11_20") (pintype "bidirectional"))
      (node (ref "U$3") (pin "P$69") (pinfunction "P$69_P$69") (pintype "bidirectional"))
    )
    (net (code "104") (name "P$70") (class "Default")
      (node (ref "IC5") (pin "22") (pinfunction "GPA5_22") (pintype "bidirectional"))
      (node (ref "MULTI4") (pin "21") (pinfunction "CHAN10_21") (pintype "bidirectional"))
      (node (ref "U$3") (pin "P$70") (pinfunction "P$70_P$70") (pintype "bidirectional"))
    )
    (net (code "105") (name "P$71") (class "Default")
      (node (ref "IC5") (pin "23") (pinfunction "GPA6_23") (pintype "bidirectional"))
      (node (ref "MULTI4") (pin "22") (pinfunction "CHAN9_22") (pintype "bidirectional"))
      (node (ref "U$3") (pin "P$71") (pinfunction "P$71_P$71") (pintype "bidirectional"))
    )
    (net (code "106") (name "P$72") (class "Default")
      (node (ref "IC5") (pin "24") (pinfunction "GPA7_24") (pintype "bidirectional"))
      (node (ref "MULTI4") (pin "23") (pinfunction "CHAN8_23") (pintype "bidirectional"))
      (node (ref "U$3") (pin "P$72") (pinfunction "P$72_P$72") (pintype "bidirectional"))
    )
    (net (code "107") (name "P$73") (class "Default")
      (node (ref "IC5") (pin "25") (pinfunction "GPB0_25") (pintype "bidirectional"))
      (node (ref "MULTI4") (pin "2") (pinfunction "CHAN7_2") (pintype "bidirectional"))
      (node (ref "U$3") (pin "P$73") (pinfunction "P$73_P$73") (pintype "bidirectional"))
    )
    (net (code "108") (name "P$74") (class "Default")
      (node (ref "IC5") (pin "26") (pinfunction "GPB1_26") (pintype "bidirectional"))
      (node (ref "MULTI4") (pin "3") (pinfunction "CHAN6_3") (pintype "bidirectional"))
      (node (ref "U$3") (pin "P$74") (pinfunction "P$74_P$74") (pintype "bidirectional"))
    )
    (net (code "109") (name "P$75") (class "Default")
      (node (ref "IC5") (pin "27") (pinfunction "GPB2_27") (pintype "bidirectional"))
      (node (ref "MULTI4") (pin "4") (pinfunction "CHAN5_4") (pintype "bidirectional"))
      (node (ref "U$3") (pin "P$75") (pinfunction "P$75_P$75") (pintype "bidirectional"))
    )
    (net (code "110") (name "P$76") (class "Default")
      (node (ref "IC5") (pin "28") (pinfunction "GPB3_28") (pintype "bidirectional"))
      (node (ref "MULTI4") (pin "5") (pinfunction "CHAN4_5") (pintype "bidirectional"))
      (node (ref "U$3") (pin "P$76") (pinfunction "P$76_P$76") (pintype "bidirectional"))
    )
    (net (code "111") (name "P$77") (class "Default")
      (node (ref "IC5") (pin "1") (pinfunction "GPB4_1") (pintype "bidirectional"))
      (node (ref "MULTI4") (pin "6") (pinfunction "CHAN3_6") (pintype "bidirectional"))
      (node (ref "U$3") (pin "P$77") (pinfunction "P$77_P$77") (pintype "bidirectional"))
    )
    (net (code "112") (name "P$78") (class "Default")
      (node (ref "IC5") (pin "2") (pinfunction "GPB5_2") (pintype "bidirectional"))
      (node (ref "MULTI4") (pin "7") (pinfunction "CHAN2_7") (pintype "bidirectional"))
      (node (ref "U$3") (pin "P$78") (pinfunction "P$78_P$78") (pintype "bidirectional"))
    )
    (net (code "113") (name "P$79") (class "Default")
      (node (ref "IC5") (pin "3") (pinfunction "GPB6_3") (pintype "bidirectional"))
      (node (ref "MULTI4") (pin "8") (pinfunction "CHAN1_8") (pintype "bidirectional"))
      (node (ref "U$3") (pin "P$79") (pinfunction "P$79_P$79") (pintype "bidirectional"))
    )
    (net (code "114") (name "P$80") (class "Default")
      (node (ref "IC5") (pin "4") (pinfunction "GPB7_4") (pintype "bidirectional"))
      (node (ref "MULTI4") (pin "9") (pinfunction "CHAN0_9") (pintype "bidirectional"))
      (node (ref "U$3") (pin "P$80") (pinfunction "P$80_P$80") (pintype "bidirectional"))
    )
    (net (code "115") (name "P$81") (class "Default")
      (node (ref "IC6") (pin "17") (pinfunction "GPA0_17") (pintype "bidirectional"))
      (node (ref "MULTI5") (pin "16") (pinfunction "CHAN15_16") (pintype "bidirectional"))
      (node (ref "U$3") (pin "P$81") (pinfunction "P$81_P$81") (pintype "bidirectional"))
    )
    (net (code "116") (name "P$82") (class "Default")
      (node (ref "IC6") (pin "18") (pinfunction "GPA1_18") (pintype "bidirectional"))
      (node (ref "MULTI5") (pin "17") (pinfunction "CHAN14_17") (pintype "bidirectional"))
      (node (ref "U$3") (pin "P$82") (pinfunction "P$82_P$82") (pintype "bidirectional"))
    )
    (net (code "117") (name "P$83") (class "Default")
      (node (ref "IC6") (pin "19") (pinfunction "GPA2_19") (pintype "bidirectional"))
      (node (ref "MULTI5") (pin "18") (pinfunction "CHAN13_18") (pintype "bidirectional"))
      (node (ref "U$3") (pin "P$83") (pinfunction "P$83_P$83") (pintype "bidirectional"))
    )
    (net (code "118") (name "P$84") (class "Default")
      (node (ref "IC6") (pin "20") (pinfunction "GPA3_20") (pintype "bidirectional"))
      (node (ref "MULTI5") (pin "19") (pinfunction "CHAN12_19") (pintype "bidirectional"))
      (node (ref "U$3") (pin "P$84") (pinfunction "P$84_P$84") (pintype "bidirectional"))
    )
    (net (code "119") (name "P$85") (class "Default")
      (node (ref "IC6") (pin "21") (pinfunction "GPA4_21") (pintype "bidirectional"))
      (node (ref "MULTI5") (pin "20") (pinfunction "CHAN11_20") (pintype "bidirectional"))
      (node (ref "U$3") (pin "P$85") (pinfunction "P$85_P$85") (pintype "bidirectional"))
    )
    (net (code "120") (name "P$86") (class "Default")
      (node (ref "IC6") (pin "22") (pinfunction "GPA5_22") (pintype "bidirectional"))
      (node (ref "MULTI5") (pin "21") (pinfunction "CHAN10_21") (pintype "bidirectional"))
      (node (ref "U$3") (pin "P$86") (pinfunction "P$86_P$86") (pintype "bidirectional"))
    )
    (net (code "121") (name "P$87") (class "Default")
      (node (ref "IC6") (pin "23") (pinfunction "GPA6_23") (pintype "bidirectional"))
      (node (ref "MULTI5") (pin "22") (pinfunction "CHAN9_22") (pintype "bidirectional"))
      (node (ref "U$3") (pin "P$87") (pinfunction "P$87_P$87") (pintype "bidirectional"))
    )
    (net (code "122") (name "P$88") (class "Default")
      (node (ref "IC6") (pin "24") (pinfunction "GPA7_24") (pintype "bidirectional"))
      (node (ref "MULTI5") (pin "23") (pinfunction "CHAN8_23") (pintype "bidirectional"))
      (node (ref "U$3") (pin "P$88") (pinfunction "P$88_P$88") (pintype "bidirectional"))
    )
    (net (code "123") (name "P$89") (class "Default")
      (node (ref "IC6") (pin "25") (pinfunction "GPB0_25") (pintype "bidirectional"))
      (node (ref "MULTI5") (pin "2") (pinfunction "CHAN7_2") (pintype "bidirectional"))
      (node (ref "U$3") (pin "P$89") (pinfunction "P$89_P$89") (pintype "bidirectional"))
    )
    (net (code "124") (name "P$90") (class "Default")
      (node (ref "IC6") (pin "26") (pinfunction "GPB1_26") (pintype "bidirectional"))
      (node (ref "MULTI5") (pin "3") (pinfunction "CHAN6_3") (pintype "bidirectional"))
      (node (ref "U$3") (pin "P$90") (pinfunction "P$90_P$90") (pintype "bidirectional"))
    )
    (net (code "125") (name "P$91") (class "Default")
      (node (ref "IC6") (pin "27") (pinfunction "GPB2_27") (pintype "bidirectional"))
      (node (ref "MULTI5") (pin "4") (pinfunction "CHAN5_4") (pintype "bidirectional"))
      (node (ref "U$3") (pin "P$91") (pinfunction "P$91_P$91") (pintype "bidirectional"))
    )
    (net (code "126") (name "P$92") (class "Default")
      (node (ref "IC6") (pin "28") (pinfunction "GPB3_28") (pintype "bidirectional"))
      (node (ref "MULTI5") (pin "5") (pinfunction "CHAN4_5") (pintype "bidirectional"))
      (node (ref "U$3") (pin "P$92") (pinfunction "P$92_P$92") (pintype "bidirectional"))
    )
    (net (code "127") (name "P$93") (class "Default")
      (node (ref "IC6") (pin "1") (pinfunction "GPB4_1") (pintype "bidirectional"))
      (node (ref "MULTI5") (pin "6") (pinfunction "CHAN3_6") (pintype "bidirectional"))
      (node (ref "U$3") (pin "P$93") (pinfunction "P$93_P$93") (pintype "bidirectional"))
    )
    (net (code "128") (name "P$94") (class "Default")
      (node (ref "IC6") (pin "2") (pinfunction "GPB5_2") (pintype "bidirectional"))
      (node (ref "MULTI5") (pin "7") (pinfunction "CHAN2_7") (pintype "bidirectional"))
      (node (ref "U$3") (pin "P$94") (pinfunction "P$94_P$94") (pintype "bidirectional"))
    )
    (net (code "129") (name "P$95") (class "Default")
      (node (ref "IC6") (pin "3") (pinfunction "GPB6_3") (pintype "bidirectional"))
      (node (ref "MULTI5") (pin "8") (pinfunction "CHAN1_8") (pintype "bidirectional"))
      (node (ref "U$3") (pin "P$95") (pinfunction "P$95_P$95") (pintype "bidirectional"))
    )
    (net (code "130") (name "P$96") (class "Default")
      (node (ref "IC6") (pin "4") (pinfunction "GPB7_4") (pintype "bidirectional"))
      (node (ref "MULTI5") (pin "9") (pinfunction "CHAN0_9") (pintype "bidirectional"))
      (node (ref "U$3") (pin "P$96") (pinfunction "P$96_P$96") (pintype "bidirectional"))
    )
    (net (code "131") (name "P$97") (class "Default")
      (node (ref "IC7") (pin "17") (pinfunction "GPA0_17") (pintype "bidirectional"))
      (node (ref "MULTI6") (pin "16") (pinfunction "CHAN15_16") (pintype "bidirectional"))
      (node (ref "U$3") (pin "P$97") (pinfunction "P$97_P$97") (pintype "bidirectional"))
    )
    (net (code "132") (name "P$98") (class "Default")
      (node (ref "IC7") (pin "18") (pinfunction "GPA1_18") (pintype "bidirectional"))
      (node (ref "MULTI6") (pin "17") (pinfunction "CHAN14_17") (pintype "bidirectional"))
      (node (ref "U$3") (pin "P$98") (pinfunction "P$98_P$98") (pintype "bidirectional"))
    )
    (net (code "133") (name "P$99") (class "Default")
      (node (ref "IC7") (pin "19") (pinfunction "GPA2_19") (pintype "bidirectional"))
      (node (ref "MULTI6") (pin "18") (pinfunction "CHAN13_18") (pintype "bidirectional"))
      (node (ref "U$3") (pin "P$99") (pinfunction "P$99_P$99") (pintype "bidirectional"))
    )
    (net (code "134") (name "P$100") (class "Default")
      (node (ref "IC7") (pin "20") (pinfunction "GPA3_20") (pintype "bidirectional"))
      (node (ref "MULTI6") (pin "19") (pinfunction "CHAN12_19") (pintype "bidirectional"))
      (node (ref "U$3") (pin "P$100") (pinfunction "P$100_P$100") (pintype "bidirectional"))
    )
    (net (code "135") (name "P$101") (class "Default")
      (node (ref "IC7") (pin "21") (pinfunction "GPA4_21") (pintype "bidirectional"))
      (node (ref "MULTI6") (pin "20") (pinfunction "CHAN11_20") (pintype "bidirectional"))
      (node (ref "U$3") (pin "P$101") (pinfunction "P$101_P$101") (pintype "bidirectional"))
    )
    (net (code "136") (name "P$102") (class "Default")
      (node (ref "IC7") (pin "22") (pinfunction "GPA5_22") (pintype "bidirectional"))
      (node (ref "MULTI6") (pin "21") (pinfunction "CHAN10_21") (pintype "bidirectional"))
      (node (ref "U$3") (pin "P$102") (pinfunction "P$102_P$102") (pintype "bidirectional"))
    )
    (net (code "137") (name "P$103") (class "Default")
      (node (ref "IC7") (pin "23") (pinfunction "GPA6_23") (pintype "bidirectional"))
      (node (ref "MULTI6") (pin "22") (pinfunction "CHAN9_22") (pintype "bidirectional"))
      (node (ref "U$3") (pin "P$103") (pinfunction "P$103_P$103") (pintype "bidirectional"))
    )
    (net (code "138") (name "P$104") (class "Default")
      (node (ref "IC7") (pin "24") (pinfunction "GPA7_24") (pintype "bidirectional"))
      (node (ref "MULTI6") (pin "23") (pinfunction "CHAN8_23") (pintype "bidirectional"))
      (node (ref "U$3") (pin "P$104") (pinfunction "P$104_P$104") (pintype "bidirectional"))
    )
    (net (code "139") (name "P$105") (class "Default")
      (node (ref "IC7") (pin "25") (pinfunction "GPB0_25") (pintype "bidirectional"))
      (node (ref "MULTI6") (pin "2") (pinfunction "CHAN7_2") (pintype "bidirectional"))
      (node (ref "U$3") (pin "P$105") (pinfunction "P$105_P$105") (pintype "bidirectional"))
    )
    (net (code "140") (name "P$106") (class "Default")
      (node (ref "IC7") (pin "26") (pinfunction "GPB1_26") (pintype "bidirectional"))
      (node (ref "MULTI6") (pin "3") (pinfunction "CHAN6_3") (pintype "bidirectional"))
      (node (ref "U$3") (pin "P$106") (pinfunction "P$106_P$106") (pintype "bidirectional"))
    )
    (net (code "141") (name "P$107") (class "Default")
      (node (ref "IC7") (pin "27") (pinfunction "GPB2_27") (pintype "bidirectional"))
      (node (ref "MULTI6") (pin "4") (pinfunction "CHAN5_4") (pintype "bidirectional"))
      (node (ref "U$3") (pin "P$107") (pinfunction "P$107_P$107") (pintype "bidirectional"))
    )
    (net (code "142") (name "P$108") (class "Default")
      (node (ref "IC7") (pin "28") (pinfunction "GPB3_28") (pintype "bidirectional"))
      (node (ref "MULTI6") (pin "5") (pinfunction "CHAN4_5") (pintype "bidirectional"))
      (node (ref "U$3") (pin "P$108") (pinfunction "P$108_P$108") (pintype "bidirectional"))
    )
    (net (code "143") (name "P$109") (class "Default")
      (node (ref "IC7") (pin "1") (pinfunction "GPB4_1") (pintype "bidirectional"))
      (node (ref "MULTI6") (pin "6") (pinfunction "CHAN3_6") (pintype "bidirectional"))
      (node (ref "U$3") (pin "P$109") (pinfunction "P$109_P$109") (pintype "bidirectional"))
    )
    (net (code "144") (name "P$110") (class "Default")
      (node (ref "IC7") (pin "2") (pinfunction "GPB5_2") (pintype "bidirectional"))
      (node (ref "MULTI6") (pin "7") (pinfunction "CHAN2_7") (pintype "bidirectional"))
      (node (ref "U$3") (pin "P$110") (pinfunction "P$110_P$110") (pintype "bidirectional"))
    )
    (net (code "145") (name "P$111") (class "Default")
      (node (ref "IC7") (pin "3") (pinfunction "GPB6_3") (pintype "bidirectional"))
      (node (ref "MULTI6") (pin "8") (pinfunction "CHAN1_8") (pintype "bidirectional"))
      (node (ref "U$3") (pin "P$111") (pinfunction "P$111_P$111") (pintype "bidirectional"))
    )
    (net (code "146") (name "P$112") (class "Default")
      (node (ref "IC7") (pin "4") (pinfunction "GPB7_4") (pintype "bidirectional"))
      (node (ref "MULTI6") (pin "9") (pinfunction "CHAN0_9") (pintype "bidirectional"))
      (node (ref "U$3") (pin "P$112") (pinfunction "P$112_P$112") (pintype "bidirectional"))
    )
    (net (code "147") (name "P$113") (class "Default")
      (node (ref "IC8") (pin "17") (pinfunction "GPA0_17") (pintype "bidirectional"))
      (node (ref "MULTI7") (pin "16") (pinfunction "CHAN15_16") (pintype "bidirectional"))
      (node (ref "U$3") (pin "P$113") (pinfunction "P$113_P$113") (pintype "bidirectional"))
    )
    (net (code "148") (name "P$114") (class "Default")
      (node (ref "IC8") (pin "18") (pinfunction "GPA1_18") (pintype "bidirectional"))
      (node (ref "MULTI7") (pin "17") (pinfunction "CHAN14_17") (pintype "bidirectional"))
      (node (ref "U$3") (pin "P$114") (pinfunction "P$114_P$114") (pintype "bidirectional"))
    )
    (net (code "149") (name "P$115") (class "Default")
      (node (ref "IC8") (pin "19") (pinfunction "GPA2_19") (pintype "bidirectional"))
      (node (ref "MULTI7") (pin "18") (pinfunction "CHAN13_18") (pintype "bidirectional"))
      (node (ref "U$3") (pin "P$115") (pinfunction "P$115_P$115") (pintype "bidirectional"))
    )
    (net (code "150") (name "P$116") (class "Default")
      (node (ref "IC8") (pin "20") (pinfunction "GPA3_20") (pintype "bidirectional"))
      (node (ref "MULTI7") (pin "19") (pinfunction "CHAN12_19") (pintype "bidirectional"))
      (node (ref "U$3") (pin "P$116") (pinfunction "P$116_P$116") (pintype "bidirectional"))
    )
    (net (code "151") (name "P$117") (class "Default")
      (node (ref "IC8") (pin "21") (pinfunction "GPA4_21") (pintype "bidirectional"))
      (node (ref "MULTI7") (pin "20") (pinfunction "CHAN11_20") (pintype "bidirectional"))
      (node (ref "U$3") (pin "P$117") (pinfunction "P$117_P$117") (pintype "bidirectional"))
    )
    (net (code "152") (name "P$118") (class "Default")
      (node (ref "IC8") (pin "22") (pinfunction "GPA5_22") (pintype "bidirectional"))
      (node (ref "MULTI7") (pin "21") (pinfunction "CHAN10_21") (pintype "bidirectional"))
      (node (ref "U$3") (pin "P$118") (pinfunction "P$118_P$118") (pintype "bidirectional"))
    )
    (net (code "153") (name "P$119") (class "Default")
      (node (ref "IC8") (pin "23") (pinfunction "GPA6_23") (pintype "bidirectional"))
      (node (ref "MULTI7") (pin "22") (pinfunction "CHAN9_22") (pintype "bidirectional"))
      (node (ref "U$3") (pin "P$119") (pinfunction "P$119_P$119") (pintype "bidirectional"))
    )
    (net (code "154") (name "P$120") (class "Default")
      (node (ref "IC8") (pin "24") (pinfunction "GPA7_24") (pintype "bidirectional"))
      (node (ref "MULTI7") (pin "23") (pinfunction "CHAN8_23") (pintype "bidirectional"))
      (node (ref "U$3") (pin "P$120") (pinfunction "P$120_P$120") (pintype "bidirectional"))
    )
    (net (code "155") (name "P$121") (class "Default")
      (node (ref "IC8") (pin "25") (pinfunction "GPB0_25") (pintype "bidirectional"))
      (node (ref "MULTI7") (pin "2") (pinfunction "CHAN7_2") (pintype "bidirectional"))
      (node (ref "U$3") (pin "P$121") (pinfunction "P$121_P$121") (pintype "bidirectional"))
    )
    (net (code "156") (name "P$122") (class "Default")
      (node (ref "IC8") (pin "26") (pinfunction "GPB1_26") (pintype "bidirectional"))
      (node (ref "MULTI7") (pin "3") (pinfunction "CHAN6_3") (pintype "bidirectional"))
      (node (ref "U$3") (pin "P$122") (pinfunction "P$122_P$122") (pintype "bidirectional"))
    )
    (net (code "157") (name "P$123") (class "Default")
      (node (ref "IC8") (pin "27") (pinfunction "GPB2_27") (pintype "bidirectional"))
      (node (ref "MULTI7") (pin "4") (pinfunction "CHAN5_4") (pintype "bidirectional"))
      (node (ref "U$3") (pin "P$123") (pinfunction "P$123_P$123") (pintype "bidirectional"))
    )
    (net (code "158") (name "P$124") (class "Default")
      (node (ref "IC8") (pin "28") (pinfunction "GPB3_28") (pintype "bidirectional"))
      (node (ref "MULTI7") (pin "5") (pinfunction "CHAN4_5") (pintype "bidirectional"))
      (node (ref "U$3") (pin "P$124") (pinfunction "P$124_P$124") (pintype "bidirectional"))
    )
    (net (code "159") (name "P$125") (class "Default")
      (node (ref "IC8") (pin "1") (pinfunction "GPB4_1") (pintype "bidirectional"))
      (node (ref "MULTI7") (pin "6") (pinfunction "CHAN3_6") (pintype "bidirectional"))
      (node (ref "U$3") (pin "P$125") (pinfunction "P$125_P$125") (pintype "bidirectional"))
    )
    (net (code "160") (name "P$126") (class "Default")
      (node (ref "IC8") (pin "2") (pinfunction "GPB5_2") (pintype "bidirectional"))
      (node (ref "MULTI7") (pin "7") (pinfunction "CHAN2_7") (pintype "bidirectional"))
      (node (ref "U$3") (pin "P$126") (pinfunction "P$126_P$126") (pintype "bidirectional"))
    )
    (net (code "161") (name "P$127") (class "Default")
      (node (ref "IC8") (pin "3") (pinfunction "GPB6_3") (pintype "bidirectional"))
      (node (ref "MULTI7") (pin "8") (pinfunction "CHAN1_8") (pintype "bidirectional"))
      (node (ref "U$3") (pin "P$127") (pinfunction "P$127_P$127") (pintype "bidirectional"))
    )
    (net (code "162") (name "P$128") (class "Default")
      (node (ref "IC8") (pin "4") (pinfunction "GPB7_4") (pintype "bidirectional"))
      (node (ref "MULTI7") (pin "9") (pinfunction "CHAN0_9") (pintype "bidirectional"))
      (node (ref "U$3") (pin "P$128") (pinfunction "P$128_P$128") (pintype "bidirectional"))
    )
    (net (code "163") (name "PIN_3") (class "Default")
      (node (ref "IC1") (pin "15") (pinfunction "INTB_15") (pintype "input"))
      (node (ref "IC2") (pin "15") (pinfunction "INTB_15") (pintype "input"))
      (node (ref "IC3") (pin "15") (pinfunction "INTB_15") (pintype "input"))
      (node (ref "IC4") (pin "15") (pinfunction "INTB_15") (pintype "input"))
      (node (ref "IC5") (pin "15") (pinfunction "INTB_15") (pintype "input"))
      (node (ref "IC6") (pin "15") (pinfunction "INTB_15") (pintype "input"))
      (node (ref "IC7") (pin "15") (pinfunction "INTB_15") (pintype "input"))
      (node (ref "IC8") (pin "15") (pinfunction "INTB_15") (pintype "input"))
    )
    (net (code "164") (name "VCC") (class "Default")
      (node (ref "C1") (pin "1") (pinfunction "1_1") (pintype "passive"))
      (node (ref "C2") (pin "1") (pinfunction "1_1") (pintype "passive"))
      (node (ref "IC1") (pin "14") (pinfunction "~{RESET}_14") (pintype "bidirectional"))
      (node (ref "IC1") (pin "5") (pinfunction "VDD_5") (pintype "power_in"))
      (node (ref "IC2") (pin "11") (pinfunction "A0_11") (pintype "bidirectional"))
      (node (ref "IC2") (pin "14") (pinfunction "~{RESET}_14") (pintype "bidirectional"))
      (node (ref "IC2") (pin "5") (pinfunction "VDD_5") (pintype "power_in"))
      (node (ref "IC3") (pin "12") (pinfunction "A1_12") (pintype "bidirectional"))
      (node (ref "IC3") (pin "14") (pinfunction "~{RESET}_14") (pintype "bidirectional"))
      (node (ref "IC3") (pin "5") (pinfunction "VDD_5") (pintype "power_in"))
      (node (ref "IC4") (pin "11") (pinfunction "A0_11") (pintype "bidirectional"))
      (node (ref "IC4") (pin "12") (pinfunction "A1_12") (pintype "bidirectional"))
      (node (ref "IC4") (pin "14") (pinfunction "~{RESET}_14") (pintype "bidirectional"))
      (node (ref "IC4") (pin "5") (pinfunction "VDD_5") (pintype "power_in"))
      (node (ref "IC5") (pin "13") (pinfunction "A2_13") (pintype "bidirectional"))
      (node (ref "IC5") (pin "14") (pinfunction "~{RESET}_14") (pintype "bidirectional"))
      (node (ref "IC5") (pin "5") (pinfunction "VDD_5") (pintype "power_in"))
      (node (ref "IC6") (pin "11") (pinfunction "A0_11") (pintype "bidirectional"))
      (node (ref "IC6") (pin "13") (pinfunction "A2_13") (pintype "bidirectional"))
      (node (ref "IC6") (pin "14") (pinfunction "~{RESET}_14") (pintype "bidirectional"))
      (node (ref "IC6") (pin "5") (pinfunction "VDD_5") (pintype "power_in"))
      (node (ref "IC7") (pin "12") (pinfunction "A1_12") (pintype "bidirectional"))
      (node (ref "IC7") (pin "13") (pinfunction "A2_13") (pintype "bidirectional"))
      (node (ref "IC7") (pin "14") (pinfunction "~{RESET}_14") (pintype "bidirectional"))
      (node (ref "IC7") (pin "5") (pinfunction "VDD_5") (pintype "power_in"))
      (node (ref "IC8") (pin "11") (pinfunction "A0_11") (pintype "bidirectional"))
      (node (ref "IC8") (pin "12") (pinfunction "A1_12") (pintype "bidirectional"))
      (node (ref "IC8") (pin "13") (pinfunction "A2_13") (pintype "bidirectional"))
      (node (ref "IC8") (pin "14") (pinfunction "~{RESET}_14") (pintype "bidirectional"))
      (node (ref "IC8") (pin "5") (pinfunction "VDD_5") (pintype "power_in"))
      (node (ref "JP3") (pin "2") (pinfunction "2_2") (pintype "passive"))
      (node (ref "MULTI0") (pin "24") (pinfunction "VCC_24") (pintype "bidirectional"))
      (node (ref "MULTI1") (pin "24") (pinfunction "VCC_24") (pintype "bidirectional"))
      (node (ref "MULTI2") (pin "24") (pinfunction "VCC_24") (pintype "bidirectional"))
      (node (ref "MULTI3") (pin "24") (pinfunction "VCC_24") (pintype "bidirectional"))
      (node (ref "MULTI4") (pin "24") (pinfunction "VCC_24") (pintype "bidirectional"))
      (node (ref "MULTI5") (pin "24") (pinfunction "VCC_24") (pintype "bidirectional"))
      (node (ref "MULTI6") (pin "24") (pinfunction "VCC_24") (pintype "bidirectional"))
      (node (ref "MULTI7") (pin "24") (pinfunction "VCC_24") (pintype "bidirectional"))
      (node (ref "R10") (pin "1") (pinfunction "1_1") (pintype "passive"))
      (node (ref "R11") (pin "1") (pinfunction "1_1") (pintype "passive"))
      (node (ref "R12") (pin "1") (pinfunction "1_1") (pintype "passive"))
      (node (ref "R13") (pin "1") (pinfunction "1_1") (pintype "passive"))
      (node (ref "R14") (pin "1") (pinfunction "1_1") (pintype "passive"))
      (node (ref "R15") (pin "1") (pinfunction "1_1") (pintype "passive"))
      (node (ref "R16") (pin "1") (pinfunction "1_1") (pintype "passive"))
      (node (ref "R17") (pin "1") (pinfunction "1_1") (pintype "passive"))
      (node (ref "R18") (pin "1") (pinfunction "1_1") (pintype "passive"))
      (node (ref "R19") (pin "1") (pinfunction "1_1") (pintype "passive"))
      (node (ref "R20") (pin "1") (pinfunction "1_1") (pintype "passive"))
      (node (ref "R21") (pin "1") (pinfunction "1_1") (pintype "passive"))
      (node (ref "R22") (pin "1") (pinfunction "1_1") (pintype "passive"))
      (node (ref "R23") (pin "1") (pinfunction "1_1") (pintype "passive"))
      (node (ref "R24") (pin "1") (pinfunction "1_1") (pintype "passive"))
      (node (ref "R25") (pin "1") (pinfunction "1_1") (pintype "passive"))
      (node (ref "U1") (pin "24") (pinfunction "VCC_24") (pintype "bidirectional"))
    )
    (net (code "165") (name "VUSB") (class "Default")
      (node (ref "B1") (pin "VUSB") (pinfunction "VUSB_VUSB") (pintype "power_in"))
    )
    (net (code "166") (name "unconnected-(B1-0{slash}RX1-Pad0)") (class "Default")
      (node (ref "B1") (pin "0") (pinfunction "0/RX1_0") (pintype "bidirectional"))
    )
    (net (code "167") (name "unconnected-(B1-1{slash}TX1-Pad1)") (class "Default")
      (node (ref "B1") (pin "1") (pinfunction "1/TX1_1") (pintype "bidirectional"))
    )
    (net (code "168") (name "unconnected-(B1-3*-Pad3)") (class "Default")
      (node (ref "B1") (pin "3") (pinfunction "3*_3") (pintype "bidirectional"))
    )
    (net (code "169") (name "unconnected-(B1-4*-Pad4)") (class "Default")
      (node (ref "B1") (pin "4") (pinfunction "4*_4") (pintype "bidirectional"))
    )
    (net (code "170") (name "unconnected-(B1-5*-Pad5)") (class "Default")
      (node (ref "B1") (pin "5") (pinfunction "5*_5") (pintype "bidirectional"))
    )
    (net (code "171") (name "unconnected-(B1-6*-Pad6)") (class "Default")
      (node (ref "B1") (pin "6") (pinfunction "6*_6") (pintype "bidirectional"))
    )
    (net (code "172") (name "unconnected-(B1-7{slash}RX3-Pad7)") (class "Default")
      (node (ref "B1") (pin "7") (pinfunction "7/RX3_7") (pintype "bidirectional"))
    )
    (net (code "173") (name "unconnected-(B1-8{slash}TX3-Pad8)") (class "Default")
      (node (ref "B1") (pin "8") (pinfunction "8/TX3_8") (pintype "bidirectional"))
    )
    (net (code "174") (name "unconnected-(B1-9*{slash}RX2-Pad9)") (class "Default")
      (node (ref "B1") (pin "9") (pinfunction "9*/RX2_9") (pintype "bidirectional"))
    )
    (net (code "175") (name "unconnected-(B1-10*{slash}TX2{slash}CS-Pad10)") (class "Default")
      (node (ref "B1") (pin "10") (pinfunction "10*/TX2/CS_10") (pintype "bidirectional"))
    )
    (net (code "176") (name "unconnected-(B1-11{slash}DOUT-Pad11)") (class "Default")
      (node (ref "B1") (pin "11") (pinfunction "11/DOUT_11") (pintype "bidirectional"))
    )
    (net (code "177") (name "unconnected-(B1-12{slash}DIN-Pad12)") (class "Default")
      (node (ref "B1") (pin "12") (pinfunction "12/DIN_12") (pintype "bidirectional"))
    )
    (net (code "178") (name "unconnected-(B1-13{slash}SCK-Pad13)") (class "Default")
      (node (ref "B1") (pin "13") (pinfunction "13/SCK_13") (pintype "bidirectional"))
    )
    (net (code "179") (name "unconnected-(B1-A0{slash}14-Pad14)") (class "Default")
      (node (ref "B1") (pin "14") (pinfunction "A0/14_14") (pintype "bidirectional"))
    )
    (net (code "180") (name "unconnected-(B1-A1{slash}15-Pad15)") (class "Default")
      (node (ref "B1") (pin "15") (pinfunction "A1/15_15") (pintype "bidirectional"))
    )
    (net (code "181") (name "unconnected-(B1-A2{slash}16-Pad16)") (class "Default")
      (node (ref "B1") (pin "16") (pinfunction "A2/16_16") (pintype "bidirectional"))
    )
    (net (code "182") (name "unconnected-(B1-A3{slash}17-Pad17)") (class "Default")
      (node (ref "B1") (pin "17") (pinfunction "A3/17_17") (pintype "bidirectional"))
    )
    (net (code "183") (name "unconnected-(B1-A4{slash}18{slash}SDA0-Pad18)") (class "Default")
      (node (ref "B1") (pin "18") (pinfunction "A4/18/SDA0_18") (pintype "bidirectional"))
    )
    (net (code "184") (name "unconnected-(B1-A5{slash}19{slash}SCL0-Pad19)") (class "Default")
      (node (ref "B1") (pin "19") (pinfunction "A5/19/SCL0_19") (pintype "bidirectional"))
    )
    (net (code "185") (name "unconnected-(B1-A6{slash}20*-Pad20)") (class "Default")
      (node (ref "B1") (pin "20") (pinfunction "A6/20*_20") (pintype "bidirectional"))
    )
    (net (code "186") (name "unconnected-(B1-A7{slash}21*-Pad21)") (class "Default")
      (node (ref "B1") (pin "21") (pinfunction "A7/21*_21") (pintype "bidirectional"))
    )
    (net (code "187") (name "unconnected-(B1-A8{slash}22*-Pad22)") (class "Default")
      (node (ref "B1") (pin "22") (pinfunction "A8/22*_22") (pintype "bidirectional"))
    )
    (net (code "188") (name "unconnected-(B1-A9{slash}23*-Pad23)") (class "Default")
      (node (ref "B1") (pin "23") (pinfunction "A9/23*_23") (pintype "bidirectional"))
    )
    (net (code "189") (name "unconnected-(B1-Pad2)") (class "Default")
      (node (ref "B1") (pin "2") (pinfunction "2_2") (pintype "bidirectional"))
    )
    (net (code "190") (name "unconnected-(B1-Pad3.3V)") (class "Default")
      (node (ref "B1") (pin "3.3V") (pinfunction "3.3V_3.3V") (pintype "power_in"))
    )
    (net (code "191") (name "unconnected-(B1-PadA10)") (class "Default")
      (node (ref "B1") (pin "A10") (pinfunction "A10_A10") (pintype "bidirectional"))
    )
    (net (code "192") (name "unconnected-(B1-PadA11)") (class "Default")
      (node (ref "B1") (pin "A11") (pinfunction "A11_A11") (pintype "bidirectional"))
    )
    (net (code "193") (name "unconnected-(B1-PadA14{slash}DAC)") (class "Default")
      (node (ref "B1") (pin "A14/DAC") (pinfunction "A14/DAC_A14/DAC") (pintype "bidirectional"))
    )
    (net (code "194") (name "unconnected-(B1-PadAREF)") (class "Default")
      (node (ref "B1") (pin "AREF") (pinfunction "AREF_AREF") (pintype "bidirectional"))
    )
    (net (code "195") (name "unconnected-(B1-PadGND)") (class "Default")
      (node (ref "B1") (pin "GND") (pinfunction "GND_GND") (pintype "power_in"))
    )
    (net (code "196") (name "unconnected-(B1-PadPROG)") (class "Default")
      (node (ref "B1") (pin "PROG") (pinfunction "PROG_PROG") (pintype "bidirectional"))
    )
    (net (code "197") (name "unconnected-(B1-PadVBAT)") (class "Default")
      (node (ref "B1") (pin "VBAT") (pinfunction "VBAT_VBAT") (pintype "power_in"))
    )
    (net (code "198") (name "unconnected-(B1-PadVIN)") (class "Default")
      (node (ref "B1") (pin "VIN") (pinfunction "VIN_VIN") (pintype "power_in"))
    )
    (net (code "199") (name "unconnected-(IC1-EP-Pad29)") (class "Default")
      (node (ref "IC1") (pin "29") (pinfunction "EP_29") (pintype "bidirectional"))
    )
    (net (code "200") (name "unconnected-(IC1-INTA-Pad16)") (class "Default")
      (node (ref "IC1") (pin "16") (pinfunction "INTA_16") (pintype "input"))
    )
    (net (code "201") (name "unconnected-(IC1-NC_1-Pad7)") (class "Default")
      (node (ref "IC1") (pin "7") (pinfunction "NC_1_7") (pintype "bidirectional"))
    )
    (net (code "202") (name "unconnected-(IC1-NC_2-Pad10)") (class "Default")
      (node (ref "IC1") (pin "10") (pinfunction "NC_2_10") (pintype "bidirectional"))
    )
    (net (code "203") (name "unconnected-(IC2-EP-Pad29)") (class "Default")
      (node (ref "IC2") (pin "29") (pinfunction "EP_29") (pintype "bidirectional"))
    )
    (net (code "204") (name "unconnected-(IC2-INTA-Pad16)") (class "Default")
      (node (ref "IC2") (pin "16") (pinfunction "INTA_16") (pintype "input"))
    )
    (net (code "205") (name "unconnected-(IC2-NC_1-Pad7)") (class "Default")
      (node (ref "IC2") (pin "7") (pinfunction "NC_1_7") (pintype "bidirectional"))
    )
    (net (code "206") (name "unconnected-(IC2-NC_2-Pad10)") (class "Default")
      (node (ref "IC2") (pin "10") (pinfunction "NC_2_10") (pintype "bidirectional"))
    )
    (net (code "207") (name "unconnected-(IC3-EP-Pad29)") (class "Default")
      (node (ref "IC3") (pin "29") (pinfunction "EP_29") (pintype "bidirectional"))
    )
    (net (code "208") (name "unconnected-(IC3-INTA-Pad16)") (class "Default")
      (node (ref "IC3") (pin "16") (pinfunction "INTA_16") (pintype "input"))
    )
    (net (code "209") (name "unconnected-(IC3-NC_1-Pad7)") (class "Default")
      (node (ref "IC3") (pin "7") (pinfunction "NC_1_7") (pintype "bidirectional"))
    )
    (net (code "210") (name "unconnected-(IC3-NC_2-Pad10)") (class "Default")
      (node (ref "IC3") (pin "10") (pinfunction "NC_2_10") (pintype "bidirectional"))
    )
    (net (code "211") (name "unconnected-(IC4-EP-Pad29)") (class "Default")
      (node (ref "IC4") (pin "29") (pinfunction "EP_29") (pintype "bidirectional"))
    )
    (net (code "212") (name "unconnected-(IC4-INTA-Pad16)") (class "Default")
      (node (ref "IC4") (pin "16") (pinfunction "INTA_16") (pintype "input"))
    )
    (net (code "213") (name "unconnected-(IC4-NC_1-Pad7)") (class "Default")
      (node (ref "IC4") (pin "7") (pinfunction "NC_1_7") (pintype "bidirectional"))
    )
    (net (code "214") (name "unconnected-(IC4-NC_2-Pad10)") (class "Default")
      (node (ref "IC4") (pin "10") (pinfunction "NC_2_10") (pintype "bidirectional"))
    )
    (net (code "215") (name "unconnected-(IC5-EP-Pad29)") (class "Default")
      (node (ref "IC5") (pin "29") (pinfunction "EP_29") (pintype "bidirectional"))
    )
    (net (code "216") (name "unconnected-(IC5-INTA-Pad16)") (class "Default")
      (node (ref "IC5") (pin "16") (pinfunction "INTA_16") (pintype "input"))
    )
    (net (code "217") (name "unconnected-(IC5-NC_1-Pad7)") (class "Default")
      (node (ref "IC5") (pin "7") (pinfunction "NC_1_7") (pintype "bidirectional"))
    )
    (net (code "218") (name "unconnected-(IC5-NC_2-Pad10)") (class "Default")
      (node (ref "IC5") (pin "10") (pinfunction "NC_2_10") (pintype "bidirectional"))
    )
    (net (code "219") (name "unconnected-(IC6-EP-Pad29)") (class "Default")
      (node (ref "IC6") (pin "29") (pinfunction "EP_29") (pintype "bidirectional"))
    )
    (net (code "220") (name "unconnected-(IC6-INTA-Pad16)") (class "Default")
      (node (ref "IC6") (pin "16") (pinfunction "INTA_16") (pintype "input"))
    )
    (net (code "221") (name "unconnected-(IC6-NC_1-Pad7)") (class "Default")
      (node (ref "IC6") (pin "7") (pinfunction "NC_1_7") (pintype "bidirectional"))
    )
    (net (code "222") (name "unconnected-(IC6-NC_2-Pad10)") (class "Default")
      (node (ref "IC6") (pin "10") (pinfunction "NC_2_10") (pintype "bidirectional"))
    )
    (net (code "223") (name "unconnected-(IC7-EP-Pad29)") (class "Default")
      (node (ref "IC7") (pin "29") (pinfunction "EP_29") (pintype "bidirectional"))
    )
    (net (code "224") (name "unconnected-(IC7-INTA-Pad16)") (class "Default")
      (node (ref "IC7") (pin "16") (pinfunction "INTA_16") (pintype "input"))
    )
    (net (code "225") (name "unconnected-(IC7-NC_1-Pad7)") (class "Default")
      (node (ref "IC7") (pin "7") (pinfunction "NC_1_7") (pintype "bidirectional"))
    )
    (net (code "226") (name "unconnected-(IC7-NC_2-Pad10)") (class "Default")
      (node (ref "IC7") (pin "10") (pinfunction "NC_2_10") (pintype "bidirectional"))
    )
    (net (code "227") (name "unconnected-(IC8-EP-Pad29)") (class "Default")
      (node (ref "IC8") (pin "29") (pinfunction "EP_29") (pintype "bidirectional"))
    )
    (net (code "228") (name "unconnected-(IC8-INTA-Pad16)") (class "Default")
      (node (ref "IC8") (pin "16") (pinfunction "INTA_16") (pintype "input"))
    )
    (net (code "229") (name "unconnected-(IC8-NC_1-Pad7)") (class "Default")
      (node (ref "IC8") (pin "7") (pinfunction "NC_1_7") (pintype "bidirectional"))
    )
    (net (code "230") (name "unconnected-(IC8-NC_2-Pad10)") (class "Default")
      (node (ref "IC8") (pin "10") (pinfunction "NC_2_10") (pintype "bidirectional"))
    )
  )
)
